# duckypad.net
KiCad netlist of a schematic drawn in EAGLE
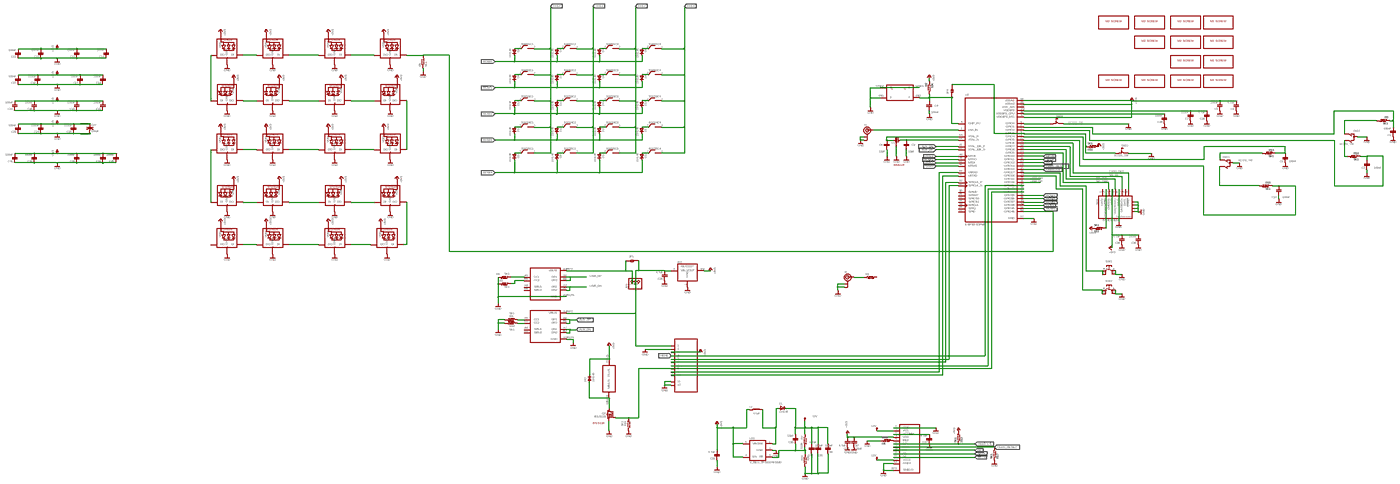
[diagram p0: schematic, sheet 1, overview]
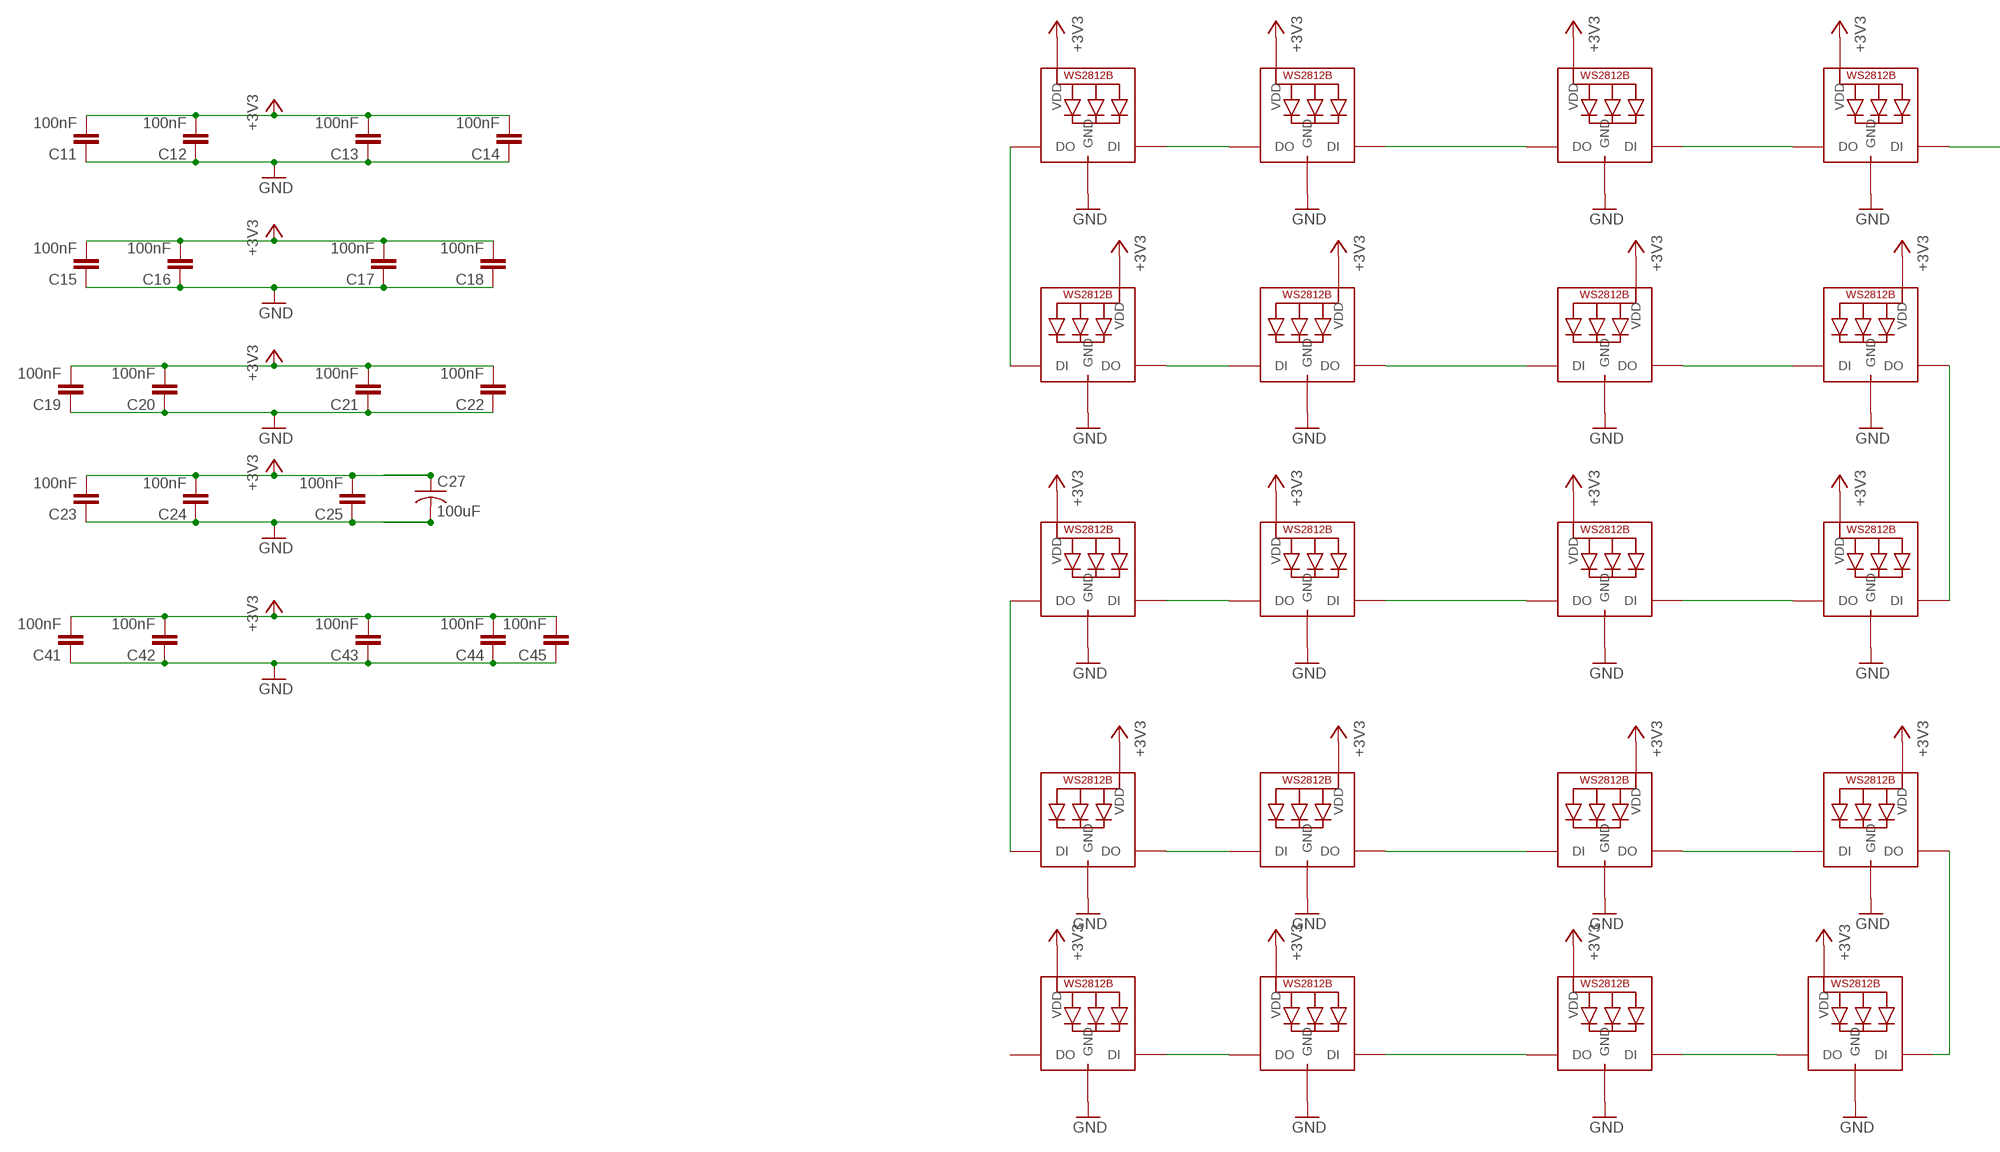
[diagram p1: schematic, sheet 1, part 1 of 4]
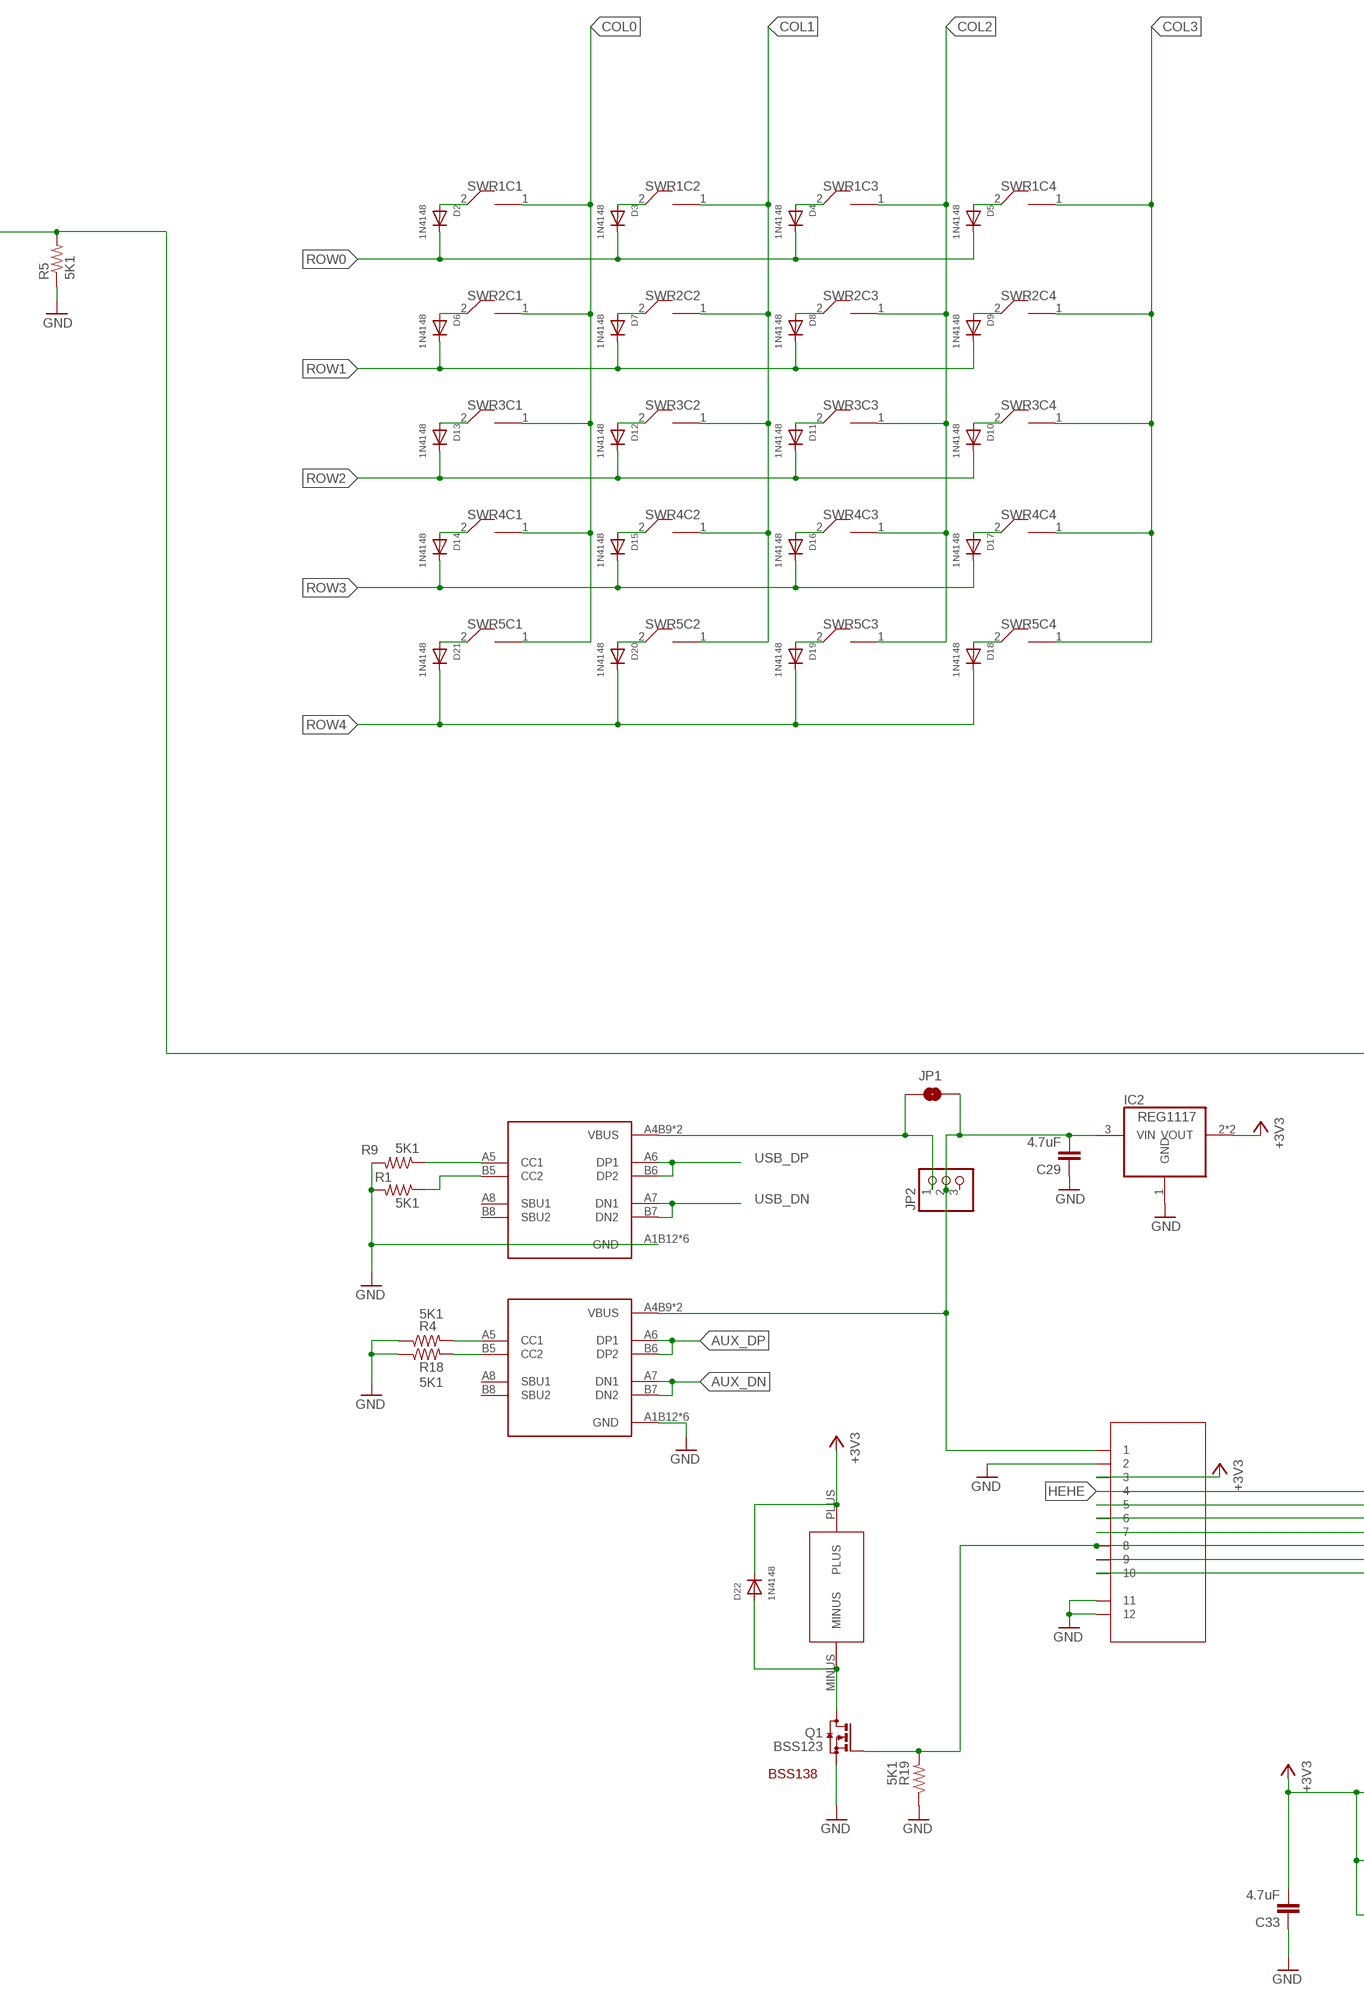
[diagram p2: schematic, sheet 1, part 2 of 4]
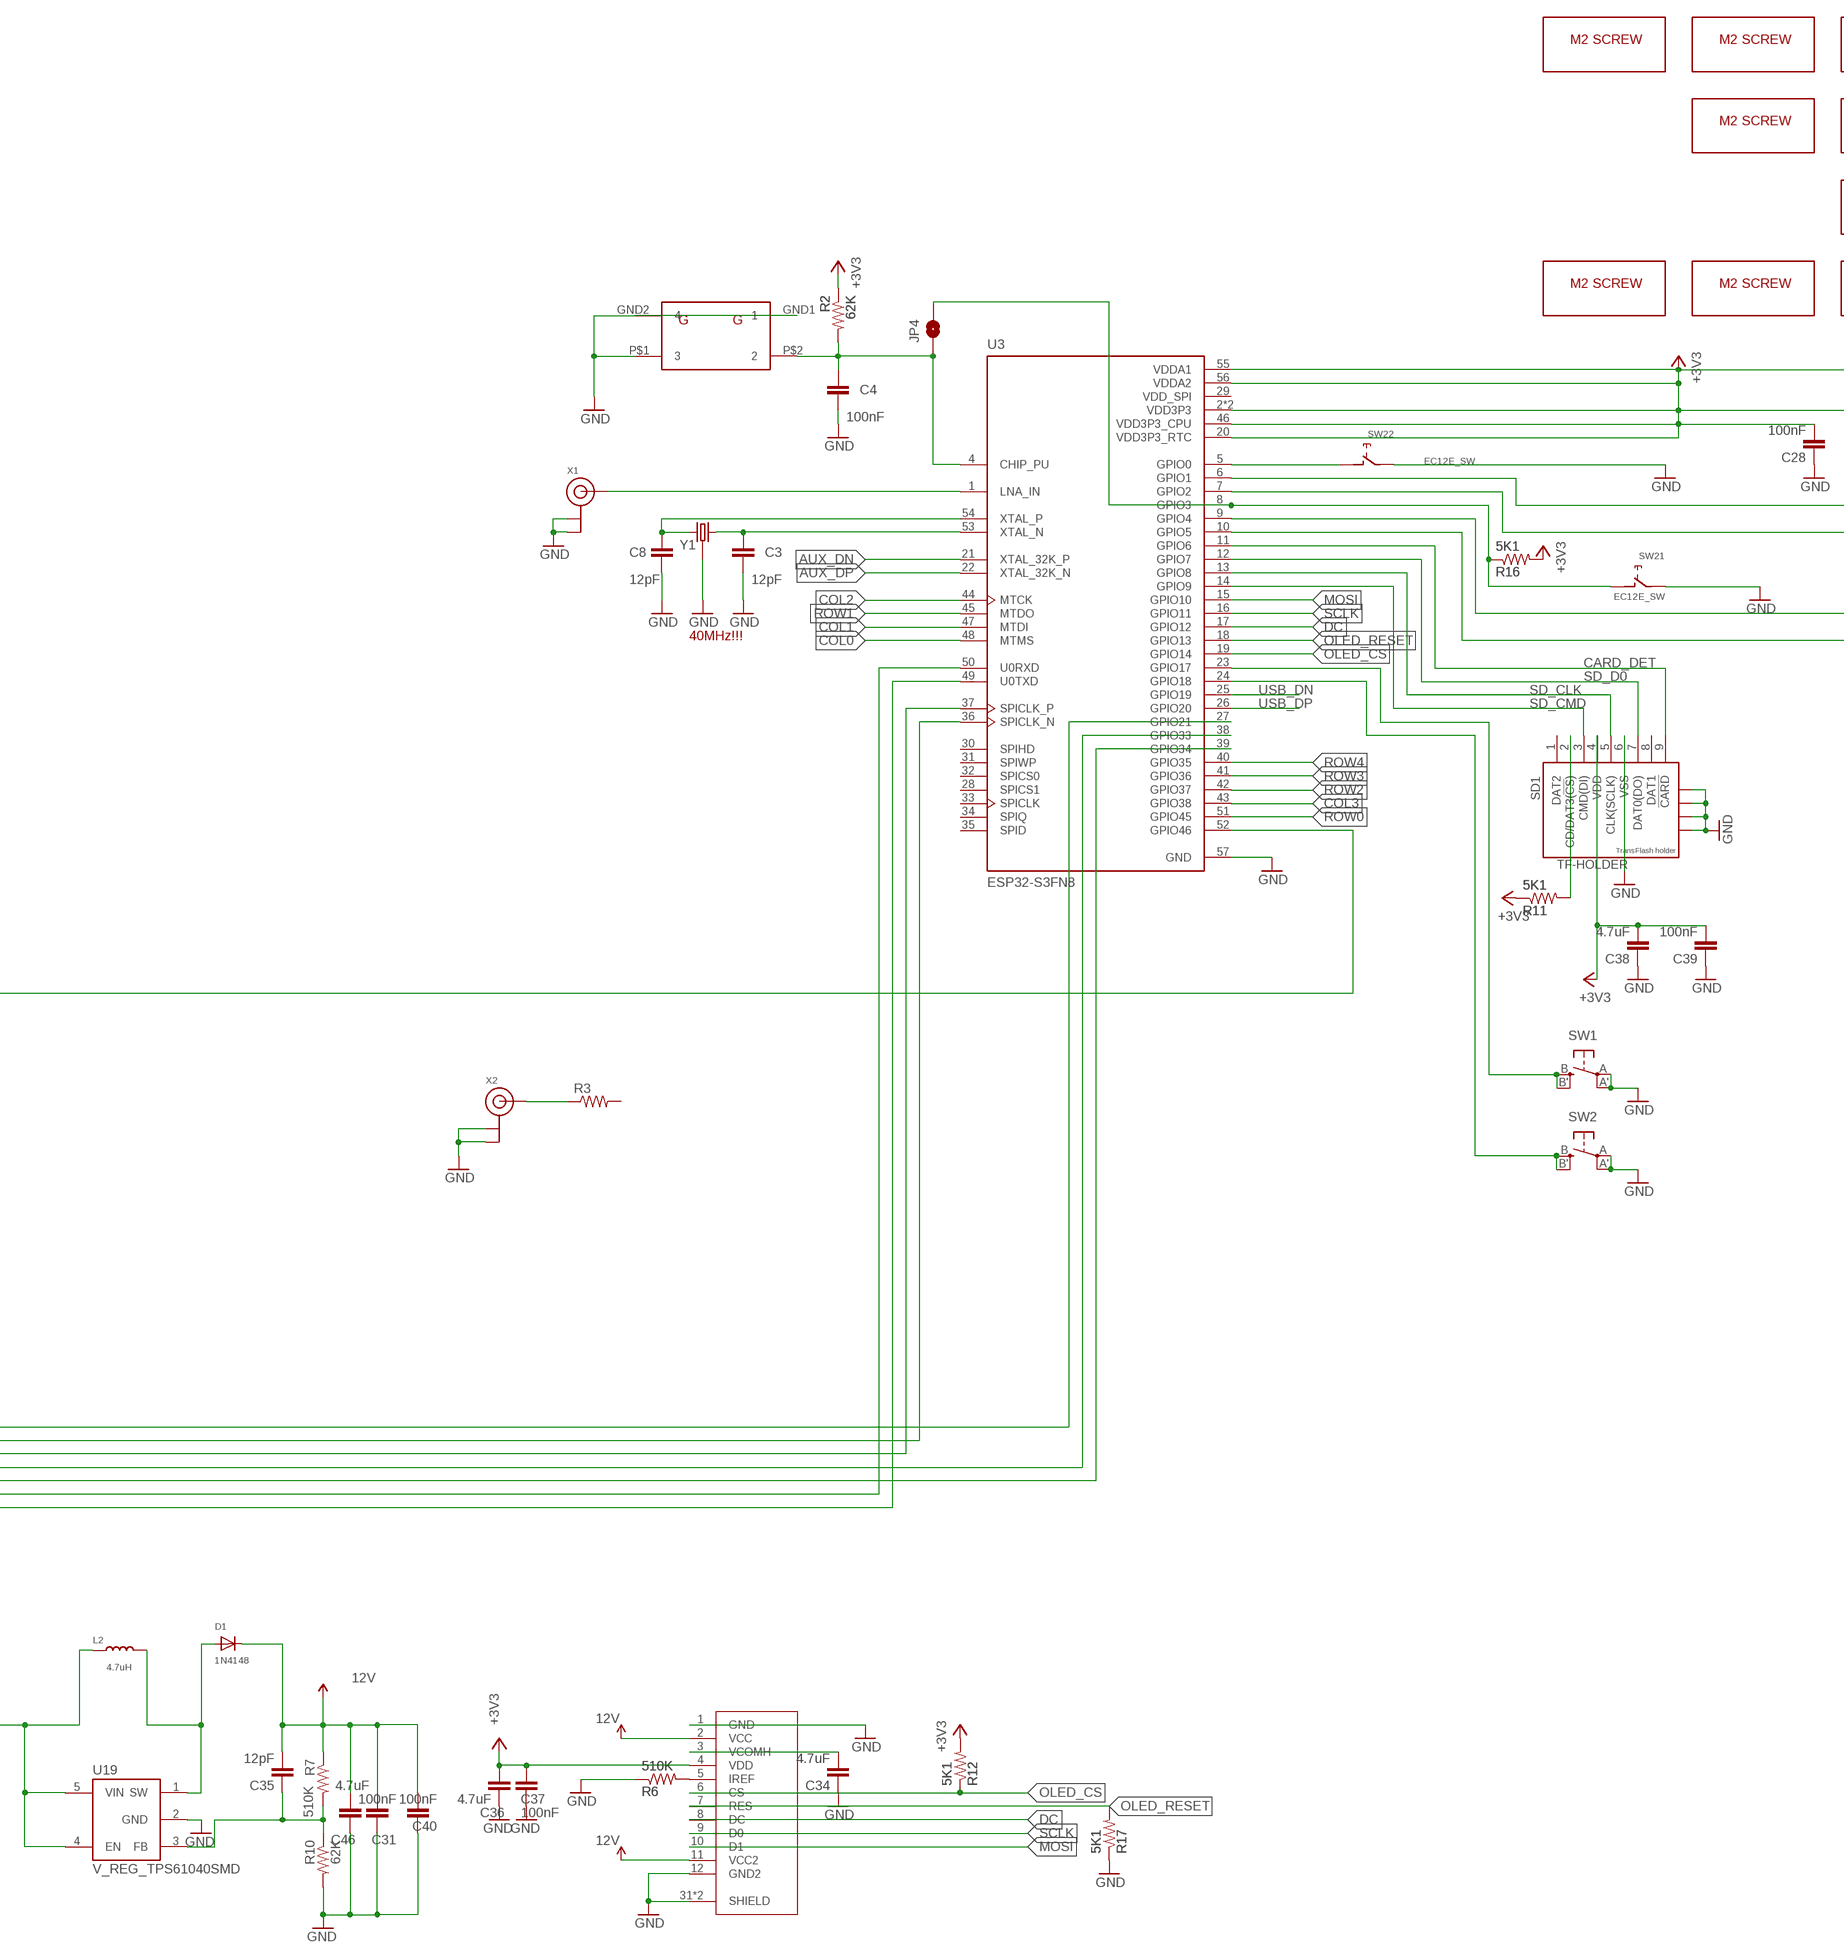
[diagram p3: schematic, sheet 1, part 3 of 4]
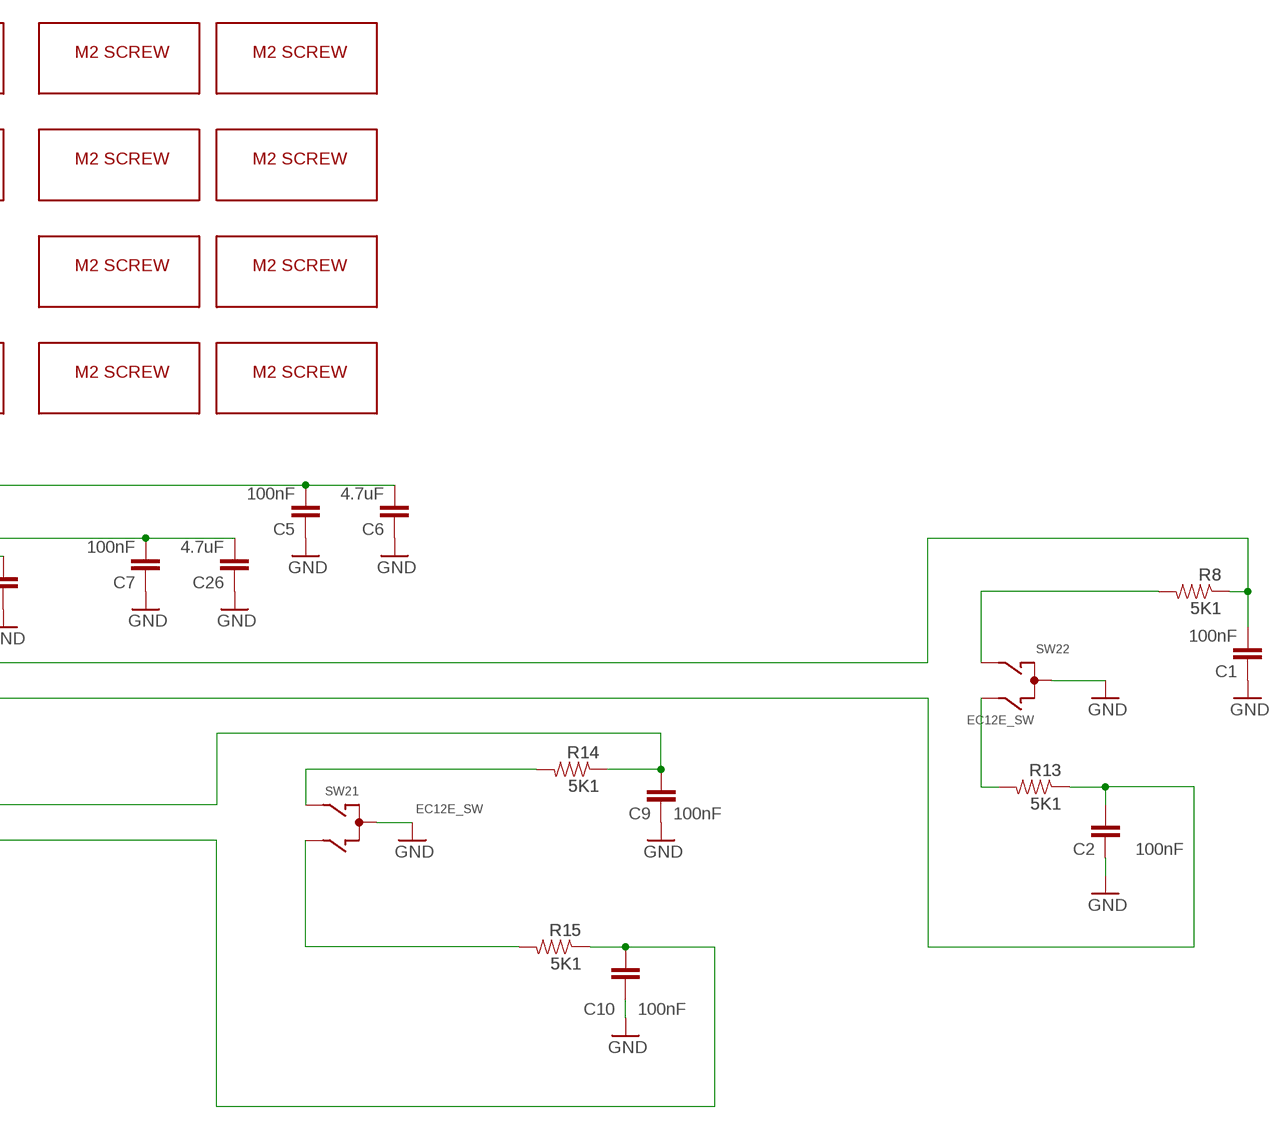
[diagram p4: schematic, sheet 1, part 4 of 4]

(export (version "E")
  (design (tool "Eeschema 10.0.6"))
  (components
    (comp (ref "BZ1")
      (value "BUZZ40402")
      (footprint "eagle-import:BUZZ")
      (libsource (lib "eagle-import") (part "BUZZ40402"))
    )
    (comp (ref "C1")
      (value "100nF")
      (footprint "eagle-import:0805")
      (libsource (lib "eagle-import") (part "CAP0805"))
    )
    (comp (ref "C2")
      (value "100nF")
      (footprint "eagle-import:0805")
      (libsource (lib "eagle-import") (part "CAP0805"))
    )
    (comp (ref "C3")
      (value "12pF")
      (footprint "eagle-import:0805")
      (libsource (lib "eagle-import") (part "CAP0805"))
    )
    (comp (ref "C4")
      (value "100nF")
      (footprint "eagle-import:0805")
      (libsource (lib "eagle-import") (part "CAP0805"))
    )
    (comp (ref "C5")
      (value "100nF")
      (footprint "eagle-import:0805")
      (libsource (lib "eagle-import") (part "CAP0805"))
    )
    (comp (ref "C6")
      (value "4.7uF")
      (footprint "eagle-import:0805")
      (libsource (lib "eagle-import") (part "CAP0805"))
    )
    (comp (ref "C7")
      (value "100nF")
      (footprint "eagle-import:0805")
      (libsource (lib "eagle-import") (part "CAP0805"))
    )
    (comp (ref "C8")
      (value "12pF")
      (footprint "eagle-import:0805")
      (libsource (lib "eagle-import") (part "CAP0805"))
    )
    (comp (ref "C9")
      (value "100nF")
      (footprint "eagle-import:0805")
      (libsource (lib "eagle-import") (part "CAP0805"))
    )
    (comp (ref "C10")
      (value "100nF")
      (footprint "eagle-import:0805")
      (libsource (lib "eagle-import") (part "CAP0805"))
    )
    (comp (ref "C11")
      (value "100nF")
      (footprint "eagle-import:0805")
      (libsource (lib "eagle-import") (part "CAP0805"))
    )
    (comp (ref "C12")
      (value "100nF")
      (footprint "eagle-import:0805")
      (libsource (lib "eagle-import") (part "CAP0805"))
    )
    (comp (ref "C13")
      (value "100nF")
      (footprint "eagle-import:0805")
      (libsource (lib "eagle-import") (part "CAP0805"))
    )
    (comp (ref "C14")
      (value "100nF")
      (footprint "eagle-import:0805")
      (libsource (lib "eagle-import") (part "CAP0805"))
    )
    (comp (ref "C15")
      (value "100nF")
      (footprint "eagle-import:0805")
      (libsource (lib "eagle-import") (part "CAP0805"))
    )
    (comp (ref "C16")
      (value "100nF")
      (footprint "eagle-import:0805")
      (libsource (lib "eagle-import") (part "CAP0805"))
    )
    (comp (ref "C17")
      (value "100nF")
      (footprint "eagle-import:0805")
      (libsource (lib "eagle-import") (part "CAP0805"))
    )
    (comp (ref "C18")
      (value "100nF")
      (footprint "eagle-import:0805")
      (libsource (lib "eagle-import") (part "CAP0805"))
    )
    (comp (ref "C19")
      (value "100nF")
      (footprint "eagle-import:0805")
      (libsource (lib "eagle-import") (part "CAP0805"))
    )
    (comp (ref "C20")
      (value "100nF")
      (footprint "eagle-import:0805")
      (libsource (lib "eagle-import") (part "CAP0805"))
    )
    (comp (ref "C21")
      (value "100nF")
      (footprint "eagle-import:0805")
      (libsource (lib "eagle-import") (part "CAP0805"))
    )
    (comp (ref "C22")
      (value "100nF")
      (footprint "eagle-import:0805")
      (libsource (lib "eagle-import") (part "CAP0805"))
    )
    (comp (ref "C23")
      (value "100nF")
      (footprint "eagle-import:0805")
      (libsource (lib "eagle-import") (part "CAP0805"))
    )
    (comp (ref "C24")
      (value "100nF")
      (footprint "eagle-import:0805")
      (libsource (lib "eagle-import") (part "CAP0805"))
    )
    (comp (ref "C25")
      (value "100nF")
      (footprint "eagle-import:0805")
      (libsource (lib "eagle-import") (part "CAP0805"))
    )
    (comp (ref "C26")
      (value "4.7uF")
      (footprint "eagle-import:0805")
      (libsource (lib "eagle-import") (part "CAP0805"))
    )
    (comp (ref "C27")
      (value "100uF")
      (footprint "eagle-import:C1210")
      (libsource (lib "eagle-import") (part "C-USC1210"))
    )
    (comp (ref "C28")
      (value "100nF")
      (footprint "eagle-import:0805")
      (libsource (lib "eagle-import") (part "CAP0805"))
    )
    (comp (ref "C29")
      (value "4.7uF")
      (footprint "eagle-import:0805")
      (libsource (lib "eagle-import") (part "CAP0805"))
    )
    (comp (ref "C31")
      (value "100nF")
      (footprint "eagle-import:0805")
      (libsource (lib "eagle-import") (part "CAP0805"))
    )
    (comp (ref "C33")
      (value "4.7uF")
      (footprint "eagle-import:0805")
      (libsource (lib "eagle-import") (part "CAP0805"))
    )
    (comp (ref "C34")
      (value "4.7uF")
      (footprint "eagle-import:0805")
      (libsource (lib "eagle-import") (part "CAP0805"))
    )
    (comp (ref "C35")
      (value "12pF")
      (footprint "eagle-import:0805")
      (libsource (lib "eagle-import") (part "CAP0805"))
    )
    (comp (ref "C36")
      (value "4.7uF")
      (footprint "eagle-import:0805")
      (libsource (lib "eagle-import") (part "CAP0805"))
    )
    (comp (ref "C37")
      (value "100nF")
      (footprint "eagle-import:0805")
      (libsource (lib "eagle-import") (part "CAP0805"))
    )
    (comp (ref "C38")
      (value "4.7uF")
      (footprint "eagle-import:0805")
      (libsource (lib "eagle-import") (part "CAP0805"))
    )
    (comp (ref "C39")
      (value "100nF")
      (footprint "eagle-import:0805")
      (libsource (lib "eagle-import") (part "CAP0805"))
    )
    (comp (ref "C40")
      (value "100nF")
      (footprint "eagle-import:0805")
      (libsource (lib "eagle-import") (part "CAP0805"))
    )
    (comp (ref "C41")
      (value "100nF")
      (footprint "eagle-import:0805")
      (libsource (lib "eagle-import") (part "CAP0805"))
    )
    (comp (ref "C42")
      (value "100nF")
      (footprint "eagle-import:0805")
      (libsource (lib "eagle-import") (part "CAP0805"))
    )
    (comp (ref "C43")
      (value "100nF")
      (footprint "eagle-import:0805")
      (libsource (lib "eagle-import") (part "CAP0805"))
    )
    (comp (ref "C44")
      (value "100nF")
      (footprint "eagle-import:0805")
      (libsource (lib "eagle-import") (part "CAP0805"))
    )
    (comp (ref "C45")
      (value "100nF")
      (footprint "eagle-import:0805")
      (libsource (lib "eagle-import") (part "CAP0805"))
    )
    (comp (ref "C46")
      (value "4.7uF")
      (footprint "eagle-import:0805")
      (libsource (lib "eagle-import") (part "CAP0805"))
    )
    (comp (ref "D1")
      (value "1N4148")
      (footprint "eagle-import:ADAFRUIT_CHANGED_SOD-123")
      (libsource (lib "eagle-import") (part "ADAFRUIT_CHANGED_DIODESOD-123"))
    )
    (comp (ref "D2")
      (value "1N4148")
      (footprint "eagle-import:ADAFRUIT_CHANGED_SOD-123")
      (libsource (lib "eagle-import") (part "ADAFRUIT_CHANGED_DIODESOD-123"))
    )
    (comp (ref "D3")
      (value "1N4148")
      (footprint "eagle-import:ADAFRUIT_CHANGED_SOD-123")
      (libsource (lib "eagle-import") (part "ADAFRUIT_CHANGED_DIODESOD-123"))
    )
    (comp (ref "D4")
      (value "1N4148")
      (footprint "eagle-import:ADAFRUIT_CHANGED_SOD-123")
      (libsource (lib "eagle-import") (part "ADAFRUIT_CHANGED_DIODESOD-123"))
    )
    (comp (ref "D5")
      (value "1N4148")
      (footprint "eagle-import:ADAFRUIT_CHANGED_SOD-123")
      (libsource (lib "eagle-import") (part "ADAFRUIT_CHANGED_DIODESOD-123"))
    )
    (comp (ref "D6")
      (value "1N4148")
      (footprint "eagle-import:ADAFRUIT_CHANGED_SOD-123")
      (libsource (lib "eagle-import") (part "ADAFRUIT_CHANGED_DIODESOD-123"))
    )
    (comp (ref "D7")
      (value "1N4148")
      (footprint "eagle-import:ADAFRUIT_CHANGED_SOD-123")
      (libsource (lib "eagle-import") (part "ADAFRUIT_CHANGED_DIODESOD-123"))
    )
    (comp (ref "D8")
      (value "1N4148")
      (footprint "eagle-import:ADAFRUIT_CHANGED_SOD-123")
      (libsource (lib "eagle-import") (part "ADAFRUIT_CHANGED_DIODESOD-123"))
    )
    (comp (ref "D9")
      (value "1N4148")
      (footprint "eagle-import:ADAFRUIT_CHANGED_SOD-123")
      (libsource (lib "eagle-import") (part "ADAFRUIT_CHANGED_DIODESOD-123"))
    )
    (comp (ref "D10")
      (value "1N4148")
      (footprint "eagle-import:ADAFRUIT_CHANGED_SOD-123")
      (libsource (lib "eagle-import") (part "ADAFRUIT_CHANGED_DIODESOD-123"))
    )
    (comp (ref "D11")
      (value "1N4148")
      (footprint "eagle-import:ADAFRUIT_CHANGED_SOD-123")
      (libsource (lib "eagle-import") (part "ADAFRUIT_CHANGED_DIODESOD-123"))
    )
    (comp (ref "D12")
      (value "1N4148")
      (footprint "eagle-import:ADAFRUIT_CHANGED_SOD-123")
      (libsource (lib "eagle-import") (part "ADAFRUIT_CHANGED_DIODESOD-123"))
    )
    (comp (ref "D13")
      (value "1N4148")
      (footprint "eagle-import:ADAFRUIT_CHANGED_SOD-123")
      (libsource (lib "eagle-import") (part "ADAFRUIT_CHANGED_DIODESOD-123"))
    )
    (comp (ref "D14")
      (value "1N4148")
      (footprint "eagle-import:ADAFRUIT_CHANGED_SOD-123")
      (libsource (lib "eagle-import") (part "ADAFRUIT_CHANGED_DIODESOD-123"))
    )
    (comp (ref "D15")
      (value "1N4148")
      (footprint "eagle-import:ADAFRUIT_CHANGED_SOD-123")
      (libsource (lib "eagle-import") (part "ADAFRUIT_CHANGED_DIODESOD-123"))
    )
    (comp (ref "D16")
      (value "1N4148")
      (footprint "eagle-import:ADAFRUIT_CHANGED_SOD-123")
      (libsource (lib "eagle-import") (part "ADAFRUIT_CHANGED_DIODESOD-123"))
    )
    (comp (ref "D17")
      (value "1N4148")
      (footprint "eagle-import:ADAFRUIT_CHANGED_SOD-123")
      (libsource (lib "eagle-import") (part "ADAFRUIT_CHANGED_DIODESOD-123"))
    )
    (comp (ref "D18")
      (value "1N4148")
      (footprint "eagle-import:ADAFRUIT_CHANGED_SOD-123")
      (libsource (lib "eagle-import") (part "ADAFRUIT_CHANGED_DIODESOD-123"))
    )
    (comp (ref "D19")
      (value "1N4148")
      (footprint "eagle-import:ADAFRUIT_CHANGED_SOD-123")
      (libsource (lib "eagle-import") (part "ADAFRUIT_CHANGED_DIODESOD-123"))
    )
    (comp (ref "D20")
      (value "1N4148")
      (footprint "eagle-import:ADAFRUIT_CHANGED_SOD-123")
      (libsource (lib "eagle-import") (part "ADAFRUIT_CHANGED_DIODESOD-123"))
    )
    (comp (ref "D21")
      (value "1N4148")
      (footprint "eagle-import:ADAFRUIT_CHANGED_SOD-123")
      (libsource (lib "eagle-import") (part "ADAFRUIT_CHANGED_DIODESOD-123"))
    )
    (comp (ref "D22")
      (value "1N4148")
      (footprint "eagle-import:ADAFRUIT_CHANGED_SOD-123")
      (libsource (lib "eagle-import") (part "ADAFRUIT_CHANGED_DIODESOD-123"))
    )
    (comp (ref "IC2")
      (value "REG1117")
      (footprint "eagle-import:SOT223")
      (libsource (lib "eagle-import") (part "REG1117"))
    )
    (comp (ref "JP1")
      (value "JUMPER-SMT_2_NO_NO-SILK")
      (footprint "eagle-import:SMT-JUMPER_2_NO_NO-SILK")
      (libsource (lib "eagle-import") (part "JUMPER-SMT_2_NO_NO-SILK"))
    )
    (comp (ref "JP2")
      (value "PINHD-1X3CB")
      (footprint "eagle-import:1X03-CLEANBIG")
      (libsource (lib "eagle-import") (part "PINHD-1X3CB"))
    )
    (comp (ref "JP4")
      (value "JUMPER-SMT_2_NO_NO-SILK")
      (footprint "eagle-import:SMT-JUMPER_2_NO_NO-SILK")
      (libsource (lib "eagle-import") (part "JUMPER-SMT_2_NO_NO-SILK"))
    )
    (comp (ref "L2")
      (value "4.7uH")
      (footprint "eagle-import:L4030")
      (libsource (lib "eagle-import") (part "L-4030"))
    )
    (comp (ref "LED_R1C1")
      (value "WS2812B")
      (footprint "eagle-import:REVERSE_MNT")
      (libsource (lib "eagle-import") (part "WS2812B"))
    )
    (comp (ref "LED_R1C2")
      (value "WS2812B")
      (footprint "eagle-import:REVERSE_MNT")
      (libsource (lib "eagle-import") (part "WS2812B"))
    )
    (comp (ref "LED_R1C3")
      (value "WS2812B")
      (footprint "eagle-import:REVERSE_MNT")
      (libsource (lib "eagle-import") (part "WS2812B"))
    )
    (comp (ref "LED_R1C4")
      (value "WS2812B")
      (footprint "eagle-import:REVERSE_MNT")
      (libsource (lib "eagle-import") (part "WS2812B"))
    )
    (comp (ref "LED_R2C1")
      (value "WS2812B")
      (footprint "eagle-import:REVERSE_MNT")
      (libsource (lib "eagle-import") (part "WS2812B"))
    )
    (comp (ref "LED_R2C2")
      (value "WS2812B")
      (footprint "eagle-import:REVERSE_MNT")
      (libsource (lib "eagle-import") (part "WS2812B"))
    )
    (comp (ref "LED_R2C3")
      (value "WS2812B")
      (footprint "eagle-import:REVERSE_MNT")
      (libsource (lib "eagle-import") (part "WS2812B"))
    )
    (comp (ref "LED_R2C4")
      (value "WS2812B")
      (footprint "eagle-import:REVERSE_MNT")
      (libsource (lib "eagle-import") (part "WS2812B"))
    )
    (comp (ref "LED_R3C1")
      (value "WS2812B")
      (footprint "eagle-import:REVERSE_MNT")
      (libsource (lib "eagle-import") (part "WS2812B"))
    )
    (comp (ref "LED_R3C2")
      (value "WS2812B")
      (footprint "eagle-import:REVERSE_MNT")
      (libsource (lib "eagle-import") (part "WS2812B"))
    )
    (comp (ref "LED_R3C3")
      (value "WS2812B")
      (footprint "eagle-import:REVERSE_MNT")
      (libsource (lib "eagle-import") (part "WS2812B"))
    )
    (comp (ref "LED_R3C4")
      (value "WS2812B")
      (footprint "eagle-import:REVERSE_MNT")
      (libsource (lib "eagle-import") (part "WS2812B"))
    )
    (comp (ref "LED_R4C1")
      (value "WS2812B")
      (footprint "eagle-import:REVERSE_MNT")
      (libsource (lib "eagle-import") (part "WS2812B"))
    )
    (comp (ref "LED_R4C2")
      (value "WS2812B")
      (footprint "eagle-import:REVERSE_MNT")
      (libsource (lib "eagle-import") (part "WS2812B"))
    )
    (comp (ref "LED_R4C3")
      (value "WS2812B")
      (footprint "eagle-import:REVERSE_MNT")
      (libsource (lib "eagle-import") (part "WS2812B"))
    )
    (comp (ref "LED_R4C4")
      (value "WS2812B")
      (footprint "eagle-import:REVERSE_MNT")
      (libsource (lib "eagle-import") (part "WS2812B"))
    )
    (comp (ref "LED_R5C1")
      (value "WS2812B")
      (footprint "eagle-import:REVERSE_MNT")
      (libsource (lib "eagle-import") (part "WS2812B"))
    )
    (comp (ref "LED_R5C2")
      (value "WS2812B")
      (footprint "eagle-import:REVERSE_MNT")
      (libsource (lib "eagle-import") (part "WS2812B"))
    )
    (comp (ref "LED_R5C3")
      (value "WS2812B")
      (footprint "eagle-import:REVERSE_MNT")
      (libsource (lib "eagle-import") (part "WS2812B"))
    )
    (comp (ref "LED_R5C4")
      (value "WS2812B")
      (footprint "eagle-import:REVERSE_MNT")
      (libsource (lib "eagle-import") (part "WS2812B"))
    )
    (comp (ref "Q1")
      (value "BSS123")
      (footprint "eagle-import:SOT23")
      (libsource (lib "eagle-import") (part "BSS123"))
    )
    (comp (ref "R1")
      (value "5K1")
      (footprint "eagle-import:0805")
      (libsource (lib "eagle-import") (part "joyAnalog_RESISTOR0805-RES"))
    )
    (comp (ref "R2")
      (value "62K")
      (footprint "eagle-import:0805")
      (libsource (lib "eagle-import") (part "joyAnalog_RESISTOR0805-RES"))
    )
    (comp (ref "R3")
      (value "R-US_R2010")
      (footprint "eagle-import:R2010")
      (libsource (lib "eagle-import") (part "R-US_R2010"))
    )
    (comp (ref "R4")
      (value "5K1")
      (footprint "eagle-import:0805")
      (libsource (lib "eagle-import") (part "joyAnalog_RESISTOR0805-RES"))
    )
    (comp (ref "R5")
      (value "5K1")
      (footprint "eagle-import:0805")
      (libsource (lib "eagle-import") (part "RESISTOR0805-RES"))
    )
    (comp (ref "R6")
      (value "510K")
      (footprint "eagle-import:0805")
      (libsource (lib "eagle-import") (part "joyAnalog_RESISTOR0805-RES"))
    )
    (comp (ref "R7")
      (value "510K")
      (footprint "eagle-import:0805")
      (libsource (lib "eagle-import") (part "joyAnalog_RESISTOR0805-RES"))
    )
    (comp (ref "R8")
      (value "5K1")
      (footprint "eagle-import:0805")
      (libsource (lib "eagle-import") (part "joyAnalog_RESISTOR0805-RES"))
    )
    (comp (ref "R9")
      (value "5K1")
      (footprint "eagle-import:0805")
      (libsource (lib "eagle-import") (part "joyAnalog_RESISTOR0805-RES"))
    )
    (comp (ref "R10")
      (value "62K")
      (footprint "eagle-import:0805")
      (libsource (lib "eagle-import") (part "joyAnalog_RESISTOR0805-RES"))
    )
    (comp (ref "R11")
      (value "5K1")
      (footprint "eagle-import:0805")
      (libsource (lib "eagle-import") (part "joyAnalog_RESISTOR0805-RES"))
    )
    (comp (ref "R12")
      (value "5K1")
      (footprint "eagle-import:0805")
      (libsource (lib "eagle-import") (part "joyAnalog_RESISTOR0805-RES"))
    )
    (comp (ref "R13")
      (value "5K1")
      (footprint "eagle-import:0805")
      (libsource (lib "eagle-import") (part "joyAnalog_RESISTOR0805-RES"))
    )
    (comp (ref "R14")
      (value "5K1")
      (footprint "eagle-import:0805")
      (libsource (lib "eagle-import") (part "joyAnalog_RESISTOR0805-RES"))
    )
    (comp (ref "R15")
      (value "5K1")
      (footprint "eagle-import:0805")
      (libsource (lib "eagle-import") (part "joyAnalog_RESISTOR0805-RES"))
    )
    (comp (ref "R16")
      (value "5K1")
      (footprint "eagle-import:0805")
      (libsource (lib "eagle-import") (part "joyAnalog_RESISTOR0805-RES"))
    )
    (comp (ref "R17")
      (value "5K1")
      (footprint "eagle-import:0805")
      (libsource (lib "eagle-import") (part "joyAnalog_RESISTOR0805-RES"))
    )
    (comp (ref "R18")
      (value "5K1")
      (footprint "eagle-import:0805")
      (libsource (lib "eagle-import") (part "joyAnalog_RESISTOR0805-RES"))
    )
    (comp (ref "R19")
      (value "5K1")
      (footprint "eagle-import:0805")
      (libsource (lib "eagle-import") (part "joyAnalog_RESISTOR0805-RES"))
    )
    (comp (ref "SD1")
      (value "TF-HOLDER")
      (footprint "eagle-import:TF-PULL")
      (libsource (lib "eagle-import") (part "TF-HOLDER"))
    )
    (comp (ref "SH1")
      (value "SH10P")
      (footprint "eagle-import:DUCKYPAD_SM12B-SSR-H-TB")
      (libsource (lib "eagle-import") (part "SH10P"))
    )
    (comp (ref "SW1")
      (value "SPST_TACT-EVQQ2")
      (footprint "eagle-import:EVQ-Q2")
      (libsource (lib "eagle-import") (part "SPST_TACT-EVQQ2"))
    )
    (comp (ref "SW2")
      (value "SPST_TACT-EVQQ2")
      (footprint "eagle-import:EVQ-Q2")
      (libsource (lib "eagle-import") (part "SPST_TACT-EVQQ2"))
    )
    (comp (ref "SW3")
      (value "3POS_SLIDE_SWITCH_324_SW")
      (footprint "eagle-import:SIDEPUSH")
      (libsource (lib "eagle-import") (part "3POS_SLIDE_SWITCH_324_SW"))
    )
    (comp (ref "SW21")
      (value "EC12E_SW")
      (footprint "eagle-import:ALPS_EC12E_SW")
      (fields (field (name "MPN") "EC12E2424407"))
      (libsource (lib "eagle-import") (part "EC12E_SW"))
    )
    (comp (ref "SW22")
      (value "EC12E_SW")
      (footprint "eagle-import:ALPS_EC12E_SW")
      (fields (field (name "MPN") "EC12E2424407"))
      (libsource (lib "eagle-import") (part "EC12E_SW"))
    )
    (comp (ref "SWR1C1")
      (value "KAILH_SWITCH_SOCKET_KAILH_SWITCH_SOCKET")
      (footprint "eagle-import:KAILH_SWITCH_SOCKET_SWITCH_SOCKET")
      (libsource (lib "eagle-import") (part "KAILH_SWITCH_SOCKET_KAILH_SWITCH_SOCKET"))
    )
    (comp (ref "SWR1C2")
      (value "KAILH_SWITCH_SOCKET_KAILH_SWITCH_SOCKET")
      (footprint "eagle-import:KAILH_SWITCH_SOCKET_SWITCH_SOCKET")
      (libsource (lib "eagle-import") (part "KAILH_SWITCH_SOCKET_KAILH_SWITCH_SOCKET"))
    )
    (comp (ref "SWR1C3")
      (value "KAILH_SWITCH_SOCKET_KAILH_SWITCH_SOCKET")
      (footprint "eagle-import:KAILH_SWITCH_SOCKET_SWITCH_SOCKET")
      (libsource (lib "eagle-import") (part "KAILH_SWITCH_SOCKET_KAILH_SWITCH_SOCKET"))
    )
    (comp (ref "SWR1C4")
      (value "KAILH_SWITCH_SOCKET_KAILH_SWITCH_SOCKET")
      (footprint "eagle-import:KAILH_SWITCH_SOCKET_SWITCH_SOCKET")
      (libsource (lib "eagle-import") (part "KAILH_SWITCH_SOCKET_KAILH_SWITCH_SOCKET"))
    )
    (comp (ref "SWR2C1")
      (value "KAILH_SWITCH_SOCKET_KAILH_SWITCH_SOCKET")
      (footprint "eagle-import:KAILH_SWITCH_SOCKET_SWITCH_SOCKET")
      (libsource (lib "eagle-import") (part "KAILH_SWITCH_SOCKET_KAILH_SWITCH_SOCKET"))
    )
    (comp (ref "SWR2C2")
      (value "KAILH_SWITCH_SOCKET_KAILH_SWITCH_SOCKET")
      (footprint "eagle-import:KAILH_SWITCH_SOCKET_SWITCH_SOCKET")
      (libsource (lib "eagle-import") (part "KAILH_SWITCH_SOCKET_KAILH_SWITCH_SOCKET"))
    )
    (comp (ref "SWR2C3")
      (value "KAILH_SWITCH_SOCKET_KAILH_SWITCH_SOCKET")
      (footprint "eagle-import:KAILH_SWITCH_SOCKET_SWITCH_SOCKET")
      (libsource (lib "eagle-import") (part "KAILH_SWITCH_SOCKET_KAILH_SWITCH_SOCKET"))
    )
    (comp (ref "SWR2C4")
      (value "KAILH_SWITCH_SOCKET_KAILH_SWITCH_SOCKET")
      (footprint "eagle-import:KAILH_SWITCH_SOCKET_SWITCH_SOCKET")
      (libsource (lib "eagle-import") (part "KAILH_SWITCH_SOCKET_KAILH_SWITCH_SOCKET"))
    )
    (comp (ref "SWR3C1")
      (value "KAILH_SWITCH_SOCKET_KAILH_SWITCH_SOCKET")
      (footprint "eagle-import:KAILH_SWITCH_SOCKET_SWITCH_SOCKET")
      (libsource (lib "eagle-import") (part "KAILH_SWITCH_SOCKET_KAILH_SWITCH_SOCKET"))
    )
    (comp (ref "SWR3C2")
      (value "KAILH_SWITCH_SOCKET_KAILH_SWITCH_SOCKET")
      (footprint "eagle-import:KAILH_SWITCH_SOCKET_SWITCH_SOCKET")
      (libsource (lib "eagle-import") (part "KAILH_SWITCH_SOCKET_KAILH_SWITCH_SOCKET"))
    )
    (comp (ref "SWR3C3")
      (value "KAILH_SWITCH_SOCKET_KAILH_SWITCH_SOCKET")
      (footprint "eagle-import:KAILH_SWITCH_SOCKET_SWITCH_SOCKET")
      (libsource (lib "eagle-import") (part "KAILH_SWITCH_SOCKET_KAILH_SWITCH_SOCKET"))
    )
    (comp (ref "SWR3C4")
      (value "KAILH_SWITCH_SOCKET_KAILH_SWITCH_SOCKET")
      (footprint "eagle-import:KAILH_SWITCH_SOCKET_SWITCH_SOCKET")
      (libsource (lib "eagle-import") (part "KAILH_SWITCH_SOCKET_KAILH_SWITCH_SOCKET"))
    )
    (comp (ref "SWR4C1")
      (value "KAILH_SWITCH_SOCKET_KAILH_SWITCH_SOCKET")
      (footprint "eagle-import:KAILH_SWITCH_SOCKET_SWITCH_SOCKET")
      (libsource (lib "eagle-import") (part "KAILH_SWITCH_SOCKET_KAILH_SWITCH_SOCKET"))
    )
    (comp (ref "SWR4C2")
      (value "KAILH_SWITCH_SOCKET_KAILH_SWITCH_SOCKET")
      (footprint "eagle-import:KAILH_SWITCH_SOCKET_SWITCH_SOCKET")
      (libsource (lib "eagle-import") (part "KAILH_SWITCH_SOCKET_KAILH_SWITCH_SOCKET"))
    )
    (comp (ref "SWR4C3")
      (value "KAILH_SWITCH_SOCKET_KAILH_SWITCH_SOCKET")
      (footprint "eagle-import:KAILH_SWITCH_SOCKET_SWITCH_SOCKET")
      (libsource (lib "eagle-import") (part "KAILH_SWITCH_SOCKET_KAILH_SWITCH_SOCKET"))
    )
    (comp (ref "SWR4C4")
      (value "KAILH_SWITCH_SOCKET_KAILH_SWITCH_SOCKET")
      (footprint "eagle-import:KAILH_SWITCH_SOCKET_SWITCH_SOCKET")
      (libsource (lib "eagle-import") (part "KAILH_SWITCH_SOCKET_KAILH_SWITCH_SOCKET"))
    )
    (comp (ref "SWR5C1")
      (value "KAILH_SWITCH_SOCKET_KAILH_SWITCH_SOCKET")
      (footprint "eagle-import:KAILH_SWITCH_SOCKET_SWITCH_SOCKET")
      (libsource (lib "eagle-import") (part "KAILH_SWITCH_SOCKET_KAILH_SWITCH_SOCKET"))
    )
    (comp (ref "SWR5C2")
      (value "KAILH_SWITCH_SOCKET_KAILH_SWITCH_SOCKET")
      (footprint "eagle-import:KAILH_SWITCH_SOCKET_SWITCH_SOCKET")
      (libsource (lib "eagle-import") (part "KAILH_SWITCH_SOCKET_KAILH_SWITCH_SOCKET"))
    )
    (comp (ref "SWR5C3")
      (value "KAILH_SWITCH_SOCKET_KAILH_SWITCH_SOCKET")
      (footprint "eagle-import:KAILH_SWITCH_SOCKET_SWITCH_SOCKET")
      (libsource (lib "eagle-import") (part "KAILH_SWITCH_SOCKET_KAILH_SWITCH_SOCKET"))
    )
    (comp (ref "SWR5C4")
      (value "KAILH_SWITCH_SOCKET_KAILH_SWITCH_SOCKET")
      (footprint "eagle-import:KAILH_SWITCH_SOCKET_SWITCH_SOCKET")
      (libsource (lib "eagle-import") (part "KAILH_SWITCH_SOCKET_KAILH_SWITCH_SOCKET"))
    )
    (comp (ref "U$2")
      (value "OLED_OLED128")
      (footprint "eagle-import:OLED_LUL_UG-2864HSWEG01_1.3_WRAPAROUND")
      (libsource (lib "eagle-import") (part "OLED_OLED128"))
    )
    (comp (ref "U$7")
      (value "M2_SCREW_DEV")
      (footprint "eagle-import:M2_SCREW_FOOT")
      (libsource (lib "eagle-import") (part "M2_SCREW_DEV"))
    )
    (comp (ref "U$8")
      (value "M2_SCREW_DEV")
      (footprint "eagle-import:M2_SCREW_FOOT")
      (libsource (lib "eagle-import") (part "M2_SCREW_DEV"))
    )
    (comp (ref "U$9")
      (value "M2_SCREW_DEV")
      (footprint "eagle-import:M2_SCREW_FOOT")
      (libsource (lib "eagle-import") (part "M2_SCREW_DEV"))
    )
    (comp (ref "U$11")
      (value "M2_SCREW_DEV")
      (footprint "eagle-import:M2_SCREW_FOOT")
      (libsource (lib "eagle-import") (part "M2_SCREW_DEV"))
    )
    (comp (ref "U$12")
      (value "M2_SCREW_DEV")
      (footprint "eagle-import:M2_SCREW_FOOT")
      (libsource (lib "eagle-import") (part "M2_SCREW_DEV"))
    )
    (comp (ref "U$13")
      (value "M2_SCREW_DEV")
      (footprint "eagle-import:M2_SCREW_FOOT")
      (libsource (lib "eagle-import") (part "M2_SCREW_DEV"))
    )
    (comp (ref "U$14")
      (value "M2_SCREW_DEV")
      (footprint "eagle-import:M2_SCREW_FOOT")
      (libsource (lib "eagle-import") (part "M2_SCREW_DEV"))
    )
    (comp (ref "U$15")
      (value "M2_SCREW_DEV")
      (footprint "eagle-import:M2_SCREW_FOOT")
      (libsource (lib "eagle-import") (part "M2_SCREW_DEV"))
    )
    (comp (ref "U$16")
      (value "M2_SCREW_DEV")
      (footprint "eagle-import:M2_SCREW_FOOT")
      (libsource (lib "eagle-import") (part "M2_SCREW_DEV"))
    )
    (comp (ref "U$17")
      (value "M2_SCREW_DEV")
      (footprint "eagle-import:M2_SCREW_FOOT")
      (libsource (lib "eagle-import") (part "M2_SCREW_DEV"))
    )
    (comp (ref "U$20")
      (value "M2_SCREW_DEV")
      (footprint "eagle-import:M2_SCREW_FOOT")
      (libsource (lib "eagle-import") (part "M2_SCREW_DEV"))
    )
    (comp (ref "U$21")
      (value "M2_SCREW_DEV")
      (footprint "eagle-import:M2_SCREW_FOOT")
      (libsource (lib "eagle-import") (part "M2_SCREW_DEV"))
    )
    (comp (ref "U$22")
      (value "M2_SCREW_DEV")
      (footprint "eagle-import:M2_SCREW_FOOT")
      (libsource (lib "eagle-import") (part "M2_SCREW_DEV"))
    )
    (comp (ref "U1")
      (value "USBC_16P")
      (footprint "eagle-import:USBC_16P_FOOT")
      (libsource (lib "eagle-import") (part "USBC_16P"))
    )
    (comp (ref "U2")
      (value "USBC_16P")
      (footprint "eagle-import:USBC_16P_FOOT")
      (libsource (lib "eagle-import") (part "USBC_16P"))
    )
    (comp (ref "U3")
      (value "ESP32-S3FN8")
      (footprint "eagle-import:QFN40P700X700X90-57N")
      (fields (field (name "MF") "Espressif Systems"))
      (libsource (lib "eagle-import") (part "ESP32-S3FN8"))
    )
    (comp (ref "U19")
      (value "V_REG_TPS61040SMD")
      (footprint "eagle-import:SOT23-5")
      (libsource (lib "eagle-import") (part "V_REG_TPS61040SMD"))
    )
    (comp (ref "X1")
      (value "ANTENNA_U.FL")
      (footprint "eagle-import:U.FL")
      (libsource (lib "eagle-import") (part "ANTENNA_U.FL"))
    )
    (comp (ref "X2")
      (value "ANTENNA_U.FL")
      (footprint "eagle-import:U.FL")
      (libsource (lib "eagle-import") (part "ANTENNA_U.FL"))
    )
    (comp (ref "Y1")
      (value "16MHz_12pF")
      (footprint "eagle-import:CRYSTAL-SMD-3.2X2.5MM")
      (libsource (lib "eagle-import") (part "CRYSTAL-26MHZSMD-3.2X2.5"))
    )
  )
  (nets
    (net (code "1") (name "+3V3") (class "Default")
      (node (ref "BZ1") (pin "PLUS") (pinfunction "PLUS_PLUS") (pintype "bidirectional"))
      (node (ref "C11") (pin "2") (pinfunction "2_2") (pintype "passive"))
      (node (ref "C12") (pin "2") (pinfunction "2_2") (pintype "passive"))
      (node (ref "C13") (pin "2") (pinfunction "2_2") (pintype "passive"))
      (node (ref "C14") (pin "2") (pinfunction "2_2") (pintype "passive"))
      (node (ref "C15") (pin "2") (pinfunction "2_2") (pintype "passive"))
      (node (ref "C16") (pin "2") (pinfunction "2_2") (pintype "passive"))
      (node (ref "C17") (pin "2") (pinfunction "2_2") (pintype "passive"))
      (node (ref "C18") (pin "2") (pinfunction "2_2") (pintype "passive"))
      (node (ref "C19") (pin "2") (pinfunction "2_2") (pintype "passive"))
      (node (ref "C20") (pin "2") (pinfunction "2_2") (pintype "passive"))
      (node (ref "C21") (pin "2") (pinfunction "2_2") (pintype "passive"))
      (node (ref "C22") (pin "2") (pinfunction "2_2") (pintype "passive"))
      (node (ref "C23") (pin "2") (pinfunction "2_2") (pintype "passive"))
      (node (ref "C24") (pin "2") (pinfunction "2_2") (pintype "passive"))
      (node (ref "C25") (pin "2") (pinfunction "2_2") (pintype "passive"))
      (node (ref "C26") (pin "2") (pinfunction "2_2") (pintype "passive"))
      (node (ref "C27") (pin "1") (pinfunction "1_1") (pintype "passive"))
      (node (ref "C28") (pin "2") (pinfunction "2_2") (pintype "passive"))
      (node (ref "C33") (pin "2") (pinfunction "2_2") (pintype "passive"))
      (node (ref "C36") (pin "2") (pinfunction "2_2") (pintype "passive"))
      (node (ref "C37") (pin "2") (pinfunction "2_2") (pintype "passive"))
      (node (ref "C38") (pin "2") (pinfunction "2_2") (pintype "passive"))
      (node (ref "C39") (pin "2") (pinfunction "2_2") (pintype "passive"))
      (node (ref "C41") (pin "2") (pinfunction "2_2") (pintype "passive"))
      (node (ref "C42") (pin "2") (pinfunction "2_2") (pintype "passive"))
      (node (ref "C43") (pin "2") (pinfunction "2_2") (pintype "passive"))
      (node (ref "C44") (pin "2") (pinfunction "2_2") (pintype "passive"))
      (node (ref "C45") (pin "2") (pinfunction "2_2") (pintype "passive"))
      (node (ref "C5") (pin "2") (pinfunction "2_2") (pintype "passive"))
      (node (ref "C6") (pin "2") (pinfunction "2_2") (pintype "passive"))
      (node (ref "C7") (pin "2") (pinfunction "2_2") (pintype "passive"))
      (node (ref "D22") (pin "C") (pinfunction "C_C") (pintype "passive"))
      (node (ref "IC2") (pin "2") (pinfunction "VOUT_2") (pintype "output"))
      (node (ref "IC2") (pin "4") (pinfunction "VOUT_4") (pintype "output"))
      (node (ref "L2") (pin "1") (pinfunction "1_1") (pintype "passive"))
      (node (ref "LED_R1C1") (pin "VDD") (pinfunction "VDD_VDD") (pintype "power_in"))
      (node (ref "LED_R1C2") (pin "VDD") (pinfunction "VDD_VDD") (pintype "power_in"))
      (node (ref "LED_R1C3") (pin "VDD") (pinfunction "VDD_VDD") (pintype "power_in"))
      (node (ref "LED_R1C4") (pin "VDD") (pinfunction "VDD_VDD") (pintype "power_in"))
      (node (ref "LED_R2C1") (pin "VDD") (pinfunction "VDD_VDD") (pintype "power_in"))
      (node (ref "LED_R2C2") (pin "VDD") (pinfunction "VDD_VDD") (pintype "power_in"))
      (node (ref "LED_R2C3") (pin "VDD") (pinfunction "VDD_VDD") (pintype "power_in"))
      (node (ref "LED_R2C4") (pin "VDD") (pinfunction "VDD_VDD") (pintype "power_in"))
      (node (ref "LED_R3C1") (pin "VDD") (pinfunction "VDD_VDD") (pintype "power_in"))
      (node (ref "LED_R3C2") (pin "VDD") (pinfunction "VDD_VDD") (pintype "power_in"))
      (node (ref "LED_R3C3") (pin "VDD") (pinfunction "VDD_VDD") (pintype "power_in"))
      (node (ref "LED_R3C4") (pin "VDD") (pinfunction "VDD_VDD") (pintype "power_in"))
      (node (ref "LED_R4C1") (pin "VDD") (pinfunction "VDD_VDD") (pintype "power_in"))
      (node (ref "LED_R4C2") (pin "VDD") (pinfunction "VDD_VDD") (pintype "power_in"))
      (node (ref "LED_R4C3") (pin "VDD") (pinfunction "VDD_VDD") (pintype "power_in"))
      (node (ref "LED_R4C4") (pin "VDD") (pinfunction "VDD_VDD") (pintype "power_in"))
      (node (ref "LED_R5C1") (pin "VDD") (pinfunction "VDD_VDD") (pintype "power_in"))
      (node (ref "LED_R5C2") (pin "VDD") (pinfunction "VDD_VDD") (pintype "power_in"))
      (node (ref "LED_R5C3") (pin "VDD") (pinfunction "VDD_VDD") (pintype "power_in"))
      (node (ref "LED_R5C4") (pin "VDD") (pinfunction "VDD_VDD") (pintype "power_in"))
      (node (ref "R11") (pin "1") (pinfunction "1_1") (pintype "passive"))
      (node (ref "R12") (pin "2") (pinfunction "2_2") (pintype "passive"))
      (node (ref "R16") (pin "2") (pinfunction "2_2") (pintype "passive"))
      (node (ref "R2") (pin "1") (pinfunction "1_1") (pintype "passive"))
      (node (ref "SD1") (pin "4") (pinfunction "VDD_4") (pintype "power_in"))
      (node (ref "SH1") (pin "3") (pinfunction "3_3") (pintype "passive"))
      (node (ref "U$2") (pin "4") (pinfunction "VDD_4") (pintype "bidirectional"))
      (node (ref "U19") (pin "4") (pinfunction "EN_4") (pintype "bidirectional"))
      (node (ref "U19") (pin "5") (pinfunction "VIN_5") (pintype "bidirectional"))
      (node (ref "U3") (pin "2") (pinfunction "VDD3P3_2") (pintype "power_in"))
      (node (ref "U3") (pin "20") (pinfunction "VDD3P3_RTC_20") (pintype "power_in"))
      (node (ref "U3") (pin "3") (pinfunction "VDD3P3_3") (pintype "power_in"))
      (node (ref "U3") (pin "46") (pinfunction "VDD3P3_CPU_46") (pintype "power_in"))
      (node (ref "U3") (pin "55") (pinfunction "VDDA1_55") (pintype "power_in"))
      (node (ref "U3") (pin "56") (pinfunction "VDDA2_56") (pintype "power_in"))
    )
    (net (code "2") (name "/CARD_DET") (class "Default")
      (node (ref "SD1") (pin "9") (pinfunction "~{CARD}_9") (pintype "passive"))
      (node (ref "U3") (pin "11") (pinfunction "GPIO6_11") (pintype "bidirectional"))
    )
    (net (code "3") (name "/SD_CLK") (class "Default")
      (node (ref "SD1") (pin "5") (pinfunction "CLK(SCLK)_5") (pintype "input"))
      (node (ref "U3") (pin "13") (pinfunction "GPIO8_13") (pintype "bidirectional"))
    )
    (net (code "4") (name "/SD_CMD") (class "Default")
      (node (ref "SD1") (pin "3") (pinfunction "CMD(DI)_3") (pintype "bidirectional"))
      (node (ref "U3") (pin "14") (pinfunction "GPIO9_14") (pintype "bidirectional"))
    )
    (net (code "5") (name "/SD_D0") (class "Default")
      (node (ref "SD1") (pin "7") (pinfunction "DAT0(DO)_7") (pintype "bidirectional"))
      (node (ref "U3") (pin "12") (pinfunction "GPIO7_12") (pintype "bidirectional"))
    )
    (net (code "6") (name "/USB_DN") (class "Default")
      (node (ref "U2") (pin "A7") (pinfunction "DN1_A7") (pintype "bidirectional"))
      (node (ref "U2") (pin "B7") (pinfunction "DN2_B7") (pintype "bidirectional"))
      (node (ref "U3") (pin "25") (pinfunction "GPIO19_25") (pintype "bidirectional"))
    )
    (net (code "7") (name "/USB_DP") (class "Default")
      (node (ref "U2") (pin "A6") (pinfunction "DP1_A6") (pintype "bidirectional"))
      (node (ref "U2") (pin "B6") (pinfunction "DP2_B6") (pintype "bidirectional"))
      (node (ref "U3") (pin "26") (pinfunction "GPIO20_26") (pintype "bidirectional"))
    )
    (net (code "8") (name "/VDD_SPI") (class "Default")
      (node (ref "U3") (pin "29") (pinfunction "VDD_SPI_29") (pintype "power_in"))
    )
    (net (code "9") (name "12V") (class "Default")
      (node (ref "C31") (pin "2") (pinfunction "2_2") (pintype "passive"))
      (node (ref "C35") (pin "2") (pinfunction "2_2") (pintype "passive"))
      (node (ref "C40") (pin "2") (pinfunction "2_2") (pintype "passive"))
      (node (ref "C46") (pin "2") (pinfunction "2_2") (pintype "passive"))
      (node (ref "D1") (pin "C") (pinfunction "C_C") (pintype "passive"))
      (node (ref "R7") (pin "1") (pinfunction "1_1") (pintype "passive"))
      (node (ref "U$2") (pin "11") (pinfunction "VCC2_11") (pintype "bidirectional"))
      (node (ref "U$2") (pin "2") (pinfunction "VCC_2") (pintype "bidirectional"))
    )
    (net (code "10") (name "AUX_DN") (class "Default")
      (node (ref "U1") (pin "A7") (pinfunction "DN1_A7") (pintype "bidirectional"))
      (node (ref "U1") (pin "B7") (pinfunction "DN2_B7") (pintype "bidirectional"))
      (node (ref "U3") (pin "21") (pinfunction "XTAL_32K_P_21") (pintype "bidirectional"))
    )
    (net (code "11") (name "AUX_DP") (class "Default")
      (node (ref "U1") (pin "A6") (pinfunction "DP1_A6") (pintype "bidirectional"))
      (node (ref "U1") (pin "B6") (pinfunction "DP2_B6") (pintype "bidirectional"))
      (node (ref "U3") (pin "22") (pinfunction "XTAL_32K_N_22") (pintype "bidirectional"))
    )
    (net (code "12") (name "COL0") (class "Default")
      (node (ref "SWR1C1") (pin "1") (pinfunction "2_1") (pintype "passive"))
      (node (ref "SWR2C1") (pin "1") (pinfunction "2_1") (pintype "passive"))
      (node (ref "SWR3C1") (pin "1") (pinfunction "2_1") (pintype "passive"))
      (node (ref "SWR4C1") (pin "1") (pinfunction "2_1") (pintype "passive"))
      (node (ref "SWR5C1") (pin "1") (pinfunction "2_1") (pintype "passive"))
      (node (ref "U3") (pin "48") (pinfunction "MTMS_48") (pintype "bidirectional"))
    )
    (net (code "13") (name "COL1") (class "Default")
      (node (ref "SWR1C2") (pin "1") (pinfunction "2_1") (pintype "passive"))
      (node (ref "SWR2C2") (pin "1") (pinfunction "2_1") (pintype "passive"))
      (node (ref "SWR3C2") (pin "1") (pinfunction "2_1") (pintype "passive"))
      (node (ref "SWR4C2") (pin "1") (pinfunction "2_1") (pintype "passive"))
      (node (ref "SWR5C2") (pin "1") (pinfunction "2_1") (pintype "passive"))
      (node (ref "U3") (pin "47") (pinfunction "MTDI_47") (pintype "bidirectional"))
    )
    (net (code "14") (name "COL2") (class "Default")
      (node (ref "SWR1C3") (pin "1") (pinfunction "2_1") (pintype "passive"))
      (node (ref "SWR2C3") (pin "1") (pinfunction "2_1") (pintype "passive"))
      (node (ref "SWR3C3") (pin "1") (pinfunction "2_1") (pintype "passive"))
      (node (ref "SWR4C3") (pin "1") (pinfunction "2_1") (pintype "passive"))
      (node (ref "SWR5C3") (pin "1") (pinfunction "2_1") (pintype "passive"))
      (node (ref "U3") (pin "44") (pinfunction "MTCK_44") (pintype "bidirectional"))
    )
    (net (code "15") (name "COL3") (class "Default")
      (node (ref "SWR1C4") (pin "1") (pinfunction "2_1") (pintype "passive"))
      (node (ref "SWR2C4") (pin "1") (pinfunction "2_1") (pintype "passive"))
      (node (ref "SWR3C4") (pin "1") (pinfunction "2_1") (pintype "passive"))
      (node (ref "SWR4C4") (pin "1") (pinfunction "2_1") (pintype "passive"))
      (node (ref "SWR5C4") (pin "1") (pinfunction "2_1") (pintype "passive"))
      (node (ref "U3") (pin "43") (pinfunction "GPIO38_43") (pintype "bidirectional"))
    )
    (net (code "16") (name "DC") (class "Default")
      (node (ref "U$2") (pin "8") (pinfunction "DC_8") (pintype "bidirectional"))
      (node (ref "U3") (pin "17") (pinfunction "GPIO12_17") (pintype "bidirectional"))
    )
    (net (code "17") (name "GND") (class "Default")
      (node (ref "C1") (pin "1") (pinfunction "1_1") (pintype "passive"))
      (node (ref "C10") (pin "1") (pinfunction "1_1") (pintype "passive"))
      (node (ref "C11") (pin "1") (pinfunction "1_1") (pintype "passive"))
      (node (ref "C12") (pin "1") (pinfunction "1_1") (pintype "passive"))
      (node (ref "C13") (pin "1") (pinfunction "1_1") (pintype "passive"))
      (node (ref "C14") (pin "1") (pinfunction "1_1") (pintype "passive"))
      (node (ref "C15") (pin "1") (pinfunction "1_1") (pintype "passive"))
      (node (ref "C16") (pin "1") (pinfunction "1_1") (pintype "passive"))
      (node (ref "C17") (pin "1") (pinfunction "1_1") (pintype "passive"))
      (node (ref "C18") (pin "1") (pinfunction "1_1") (pintype "passive"))
      (node (ref "C19") (pin "1") (pinfunction "1_1") (pintype "passive"))
      (node (ref "C2") (pin "1") (pinfunction "1_1") (pintype "passive"))
      (node (ref "C20") (pin "1") (pinfunction "1_1") (pintype "passive"))
      (node (ref "C21") (pin "1") (pinfunction "1_1") (pintype "passive"))
      (node (ref "C22") (pin "1") (pinfunction "1_1") (pintype "passive"))
      (node (ref "C23") (pin "1") (pinfunction "1_1") (pintype "passive"))
      (node (ref "C24") (pin "1") (pinfunction "1_1") (pintype "passive"))
      (node (ref "C25") (pin "1") (pinfunction "1_1") (pintype "passive"))
      (node (ref "C26") (pin "1") (pinfunction "1_1") (pintype "passive"))
      (node (ref "C27") (pin "2") (pinfunction "2_2") (pintype "passive"))
      (node (ref "C28") (pin "1") (pinfunction "1_1") (pintype "passive"))
      (node (ref "C29") (pin "1") (pinfunction "1_1") (pintype "passive"))
      (node (ref "C3") (pin "2") (pinfunction "2_2") (pintype "passive"))
      (node (ref "C31") (pin "1") (pinfunction "1_1") (pintype "passive"))
      (node (ref "C33") (pin "1") (pinfunction "1_1") (pintype "passive"))
      (node (ref "C34") (pin "1") (pinfunction "1_1") (pintype "passive"))
      (node (ref "C36") (pin "1") (pinfunction "1_1") (pintype "passive"))
      (node (ref "C37") (pin "1") (pinfunction "1_1") (pintype "passive"))
      (node (ref "C38") (pin "1") (pinfunction "1_1") (pintype "passive"))
      (node (ref "C39") (pin "1") (pinfunction "1_1") (pintype "passive"))
      (node (ref "C4") (pin "2") (pinfunction "2_2") (pintype "passive"))
      (node (ref "C40") (pin "1") (pinfunction "1_1") (pintype "passive"))
      (node (ref "C41") (pin "1") (pinfunction "1_1") (pintype "passive"))
      (node (ref "C42") (pin "1") (pinfunction "1_1") (pintype "passive"))
      (node (ref "C43") (pin "1") (pinfunction "1_1") (pintype "passive"))
      (node (ref "C44") (pin "1") (pinfunction "1_1") (pintype "passive"))
      (node (ref "C45") (pin "1") (pinfunction "1_1") (pintype "passive"))
      (node (ref "C46") (pin "1") (pinfunction "1_1") (pintype "passive"))
      (node (ref "C5") (pin "1") (pinfunction "1_1") (pintype "passive"))
      (node (ref "C6") (pin "1") (pinfunction "1_1") (pintype "passive"))
      (node (ref "C7") (pin "1") (pinfunction "1_1") (pintype "passive"))
      (node (ref "C8") (pin "2") (pinfunction "2_2") (pintype "passive"))
      (node (ref "C9") (pin "1") (pinfunction "1_1") (pintype "passive"))
      (node (ref "IC2") (pin "1") (pinfunction "GND_1") (pintype "power_in"))
      (node (ref "LED_R1C1") (pin "GND") (pinfunction "GND_GND") (pintype "power_in"))
      (node (ref "LED_R1C2") (pin "GND") (pinfunction "GND_GND") (pintype "power_in"))
      (node (ref "LED_R1C3") (pin "GND") (pinfunction "GND_GND") (pintype "power_in"))
      (node (ref "LED_R1C4") (pin "GND") (pinfunction "GND_GND") (pintype "power_in"))
      (node (ref "LED_R2C1") (pin "GND") (pinfunction "GND_GND") (pintype "power_in"))
      (node (ref "LED_R2C2") (pin "GND") (pinfunction "GND_GND") (pintype "power_in"))
      (node (ref "LED_R2C3") (pin "GND") (pinfunction "GND_GND") (pintype "power_in"))
      (node (ref "LED_R2C4") (pin "GND") (pinfunction "GND_GND") (pintype "power_in"))
      (node (ref "LED_R3C1") (pin "GND") (pinfunction "GND_GND") (pintype "power_in"))
      (node (ref "LED_R3C2") (pin "GND") (pinfunction "GND_GND") (pintype "power_in"))
      (node (ref "LED_R3C3") (pin "GND") (pinfunction "GND_GND") (pintype "power_in"))
      (node (ref "LED_R3C4") (pin "GND") (pinfunction "GND_GND") (pintype "power_in"))
      (node (ref "LED_R4C1") (pin "GND") (pinfunction "GND_GND") (pintype "power_in"))
      (node (ref "LED_R4C2") (pin "GND") (pinfunction "GND_GND") (pintype "power_in"))
      (node (ref "LED_R4C3") (pin "GND") (pinfunction "GND_GND") (pintype "power_in"))
      (node (ref "LED_R4C4") (pin "GND") (pinfunction "GND_GND") (pintype "power_in"))
      (node (ref "LED_R5C1") (pin "GND") (pinfunction "GND_GND") (pintype "power_in"))
      (node (ref "LED_R5C2") (pin "GND") (pinfunction "GND_GND") (pintype "power_in"))
      (node (ref "LED_R5C3") (pin "GND") (pinfunction "GND_GND") (pintype "power_in"))
      (node (ref "LED_R5C4") (pin "GND") (pinfunction "GND_GND") (pintype "power_in"))
      (node (ref "Q1") (pin "2") (pinfunction "S_2") (pintype "passive"))
      (node (ref "R1") (pin "2") (pinfunction "2_2") (pintype "passive"))
      (node (ref "R10") (pin "2") (pinfunction "2_2") (pintype "passive"))
      (node (ref "R17") (pin "1") (pinfunction "1_1") (pintype "passive"))
      (node (ref "R18") (pin "1") (pinfunction "1_1") (pintype "passive"))
      (node (ref "R19") (pin "1") (pinfunction "1_1") (pintype "passive"))
      (node (ref "R4") (pin "1") (pinfunction "1_1") (pintype "passive"))
      (node (ref "R5") (pin "1") (pinfunction "1_1") (pintype "passive"))
      (node (ref "R6") (pin "1") (pinfunction "1_1") (pintype "passive"))
      (node (ref "R9") (pin "2") (pinfunction "2_2") (pintype "passive"))
      (node (ref "SD1") (pin "6") (pinfunction "VSS_6") (pintype "power_in"))
      (node (ref "SD1") (pin "S1") (pinfunction "S1_S1") (pintype "passive"))
      (node (ref "SD1") (pin "S2") (pinfunction "S2_S2") (pintype "passive"))
      (node (ref "SD1") (pin "S3") (pinfunction "S3_S3") (pintype "passive"))
      (node (ref "SD1") (pin "S4") (pinfunction "S4_S4") (pintype "passive"))
      (node (ref "SH1") (pin "2") (pinfunction "2_2") (pintype "passive"))
      (node (ref "SH1") (pin "FIT@1") (pinfunction "11_FIT@1") (pintype "passive"))
      (node (ref "SH1") (pin "FIT@2") (pinfunction "12_FIT@2") (pintype "passive"))
      (node (ref "SW1") (pin "A") (pinfunction "P_A") (pintype "passive"))
      (node (ref "SW1") (pin "A'") (pinfunction "P1_A'") (pintype "passive"))
      (node (ref "SW2") (pin "A") (pinfunction "P_A") (pintype "passive"))
      (node (ref "SW2") (pin "A'") (pinfunction "P1_A'") (pintype "passive"))
      (node (ref "SW21") (pin "C") (pinfunction "C_C") (pintype "passive"))
      (node (ref "SW21") (pin "E") (pinfunction "2_E") (pintype "passive"))
      (node (ref "SW22") (pin "C") (pinfunction "C_C") (pintype "passive"))
      (node (ref "SW22") (pin "E") (pinfunction "2_E") (pintype "passive"))
      (node (ref "SW3") (pin "GND1") (pinfunction "1_GND1") (pintype "bidirectional"))
      (node (ref "SW3") (pin "GND2") (pinfunction "4_GND2") (pintype "bidirectional"))
      (node (ref "SW3") (pin "P$1") (pinfunction "3_P$1") (pintype "bidirectional"))
      (node (ref "U$2") (pin "1") (pinfunction "GND_1") (pintype "bidirectional"))
      (node (ref "U$2") (pin "12") (pinfunction "GND2_12") (pintype "bidirectional"))
      (node (ref "U$2") (pin "31") (pinfunction "SHIELD_31") (pintype "bidirectional"))
      (node (ref "U$2") (pin "32") (pinfunction "SHIELD_32") (pintype "bidirectional"))
      (node (ref "U1") (pin "A1B12") (pinfunction "GND_A1B12") (pintype "bidirectional"))
      (node (ref "U1") (pin "B11A12") (pinfunction "GND_B11A12") (pintype "bidirectional"))
      (node (ref "U1") (pin "P$13") (pinfunction "GND_P$13") (pintype "bidirectional"))
      (node (ref "U1") (pin "P$14") (pinfunction "GND_P$14") (pintype "bidirectional"))
      (node (ref "U1") (pin "P$15") (pinfunction "GND_P$15") (pintype "bidirectional"))
      (node (ref "U1") (pin "P$16") (pinfunction "GND_P$16") (pintype "bidirectional"))
      (node (ref "U19") (pin "2") (pinfunction "GND_2") (pintype "bidirectional"))
      (node (ref "U2") (pin "A1B12") (pinfunction "GND_A1B12") (pintype "bidirectional"))
      (node (ref "U2") (pin "B11A12") (pinfunction "GND_B11A12") (pintype "bidirectional"))
      (node (ref "U2") (pin "P$13") (pinfunction "GND_P$13") (pintype "bidirectional"))
      (node (ref "U2") (pin "P$14") (pinfunction "GND_P$14") (pintype "bidirectional"))
      (node (ref "U2") (pin "P$15") (pinfunction "GND_P$15") (pintype "bidirectional"))
      (node (ref "U2") (pin "P$16") (pinfunction "GND_P$16") (pintype "bidirectional"))
      (node (ref "U3") (pin "57") (pinfunction "GND_57") (pintype "power_in"))
      (node (ref "X1") (pin "1") (pinfunction "GND_1") (pintype "passive"))
      (node (ref "X1") (pin "2") (pinfunction "GND_2") (pintype "passive"))
      (node (ref "X2") (pin "1") (pinfunction "GND_1") (pintype "passive"))
      (node (ref "X2") (pin "2") (pinfunction "GND_2") (pintype "passive"))
      (node (ref "Y1") (pin "2") (pinfunction "3_2") (pintype "passive"))
      (node (ref "Y1") (pin "4") (pinfunction "3_4") (pintype "passive"))
    )
    (net (code "18") (name "HEHE") (class "Default")
      (node (ref "SH1") (pin "4") (pinfunction "4_4") (pintype "passive"))
      (node (ref "U3") (pin "27") (pinfunction "GPIO21_27") (pintype "bidirectional"))
    )
    (net (code "19") (name "MOSI") (class "Default")
      (node (ref "U$2") (pin "10") (pinfunction "D1_10") (pintype "bidirectional"))
      (node (ref "U3") (pin "15") (pinfunction "GPIO10_15") (pintype "bidirectional"))
    )
    (net (code "20") (name "Net-(IC2-VIN)") (class "Default")
      (node (ref "C29") (pin "2") (pinfunction "2_2") (pintype "passive"))
      (node (ref "IC2") (pin "3") (pinfunction "VIN_3") (pintype "input"))
      (node (ref "JP1") (pin "2") (pinfunction "2_2") (pintype "passive"))
      (node (ref "JP2") (pin "2") (pinfunction "2_2") (pintype "passive"))
      (node (ref "SH1") (pin "1") (pinfunction "1_1") (pintype "passive"))
      (node (ref "U1") (pin "A4B9") (pinfunction "VBUS_A4B9") (pintype "bidirectional"))
      (node (ref "U1") (pin "B4A9") (pinfunction "VBUS_B4A9") (pintype "bidirectional"))
    )
    (net (code "21") (name "Net-(JP1-Pad1)") (class "Default")
      (node (ref "JP1") (pin "1") (pinfunction "1_1") (pintype "passive"))
      (node (ref "JP2") (pin "1") (pinfunction "1_1") (pintype "passive"))
      (node (ref "U2") (pin "A4B9") (pinfunction "VBUS_A4B9") (pintype "bidirectional"))
      (node (ref "U2") (pin "B4A9") (pinfunction "VBUS_B4A9") (pintype "bidirectional"))
    )
    (net (code "22") (name "Net-(LED_R1C1-DI)") (class "Default")
      (node (ref "LED_R1C1") (pin "DIN") (pinfunction "DI_DIN") (pintype "input"))
      (node (ref "LED_R1C2") (pin "DOUT") (pinfunction "DO_DOUT") (pintype "output"))
    )
    (net (code "23") (name "Net-(LED_R1C1-DO)") (class "Default")
      (node (ref "LED_R1C1") (pin "DOUT") (pinfunction "DO_DOUT") (pintype "output"))
      (node (ref "LED_R2C1") (pin "DIN") (pinfunction "DI_DIN") (pintype "input"))
    )
    (net (code "24") (name "Net-(LED_R1C2-DI)") (class "Default")
      (node (ref "LED_R1C2") (pin "DIN") (pinfunction "DI_DIN") (pintype "input"))
      (node (ref "LED_R1C3") (pin "DOUT") (pinfunction "DO_DOUT") (pintype "output"))
    )
    (net (code "25") (name "Net-(LED_R1C3-DI)") (class "Default")
      (node (ref "LED_R1C3") (pin "DIN") (pinfunction "DI_DIN") (pintype "input"))
      (node (ref "LED_R1C4") (pin "DOUT") (pinfunction "DO_DOUT") (pintype "output"))
    )
    (net (code "26") (name "Net-(LED_R1C4-DI)") (class "Default")
      (node (ref "LED_R1C4") (pin "DIN") (pinfunction "DI_DIN") (pintype "input"))
      (node (ref "R5") (pin "2") (pinfunction "2_2") (pintype "passive"))
      (node (ref "U3") (pin "52") (pinfunction "GPIO46_52") (pintype "bidirectional"))
    )
    (net (code "27") (name "Net-(LED_R2C1-DO)") (class "Default")
      (node (ref "LED_R2C1") (pin "DOUT") (pinfunction "DO_DOUT") (pintype "output"))
      (node (ref "LED_R2C2") (pin "DIN") (pinfunction "DI_DIN") (pintype "input"))
    )
    (net (code "28") (name "Net-(LED_R2C2-DO)") (class "Default")
      (node (ref "LED_R2C2") (pin "DOUT") (pinfunction "DO_DOUT") (pintype "output"))
      (node (ref "LED_R2C3") (pin "DIN") (pinfunction "DI_DIN") (pintype "input"))
    )
    (net (code "29") (name "Net-(LED_R2C3-DO)") (class "Default")
      (node (ref "LED_R2C3") (pin "DOUT") (pinfunction "DO_DOUT") (pintype "output"))
      (node (ref "LED_R2C4") (pin "DIN") (pinfunction "DI_DIN") (pintype "input"))
    )
    (net (code "30") (name "Net-(LED_R2C4-DO)") (class "Default")
      (node (ref "LED_R2C4") (pin "DOUT") (pinfunction "DO_DOUT") (pintype "output"))
      (node (ref "LED_R3C4") (pin "DIN") (pinfunction "DI_DIN") (pintype "input"))
    )
    (net (code "31") (name "Net-(LED_R3C1-DI)") (class "Default")
      (node (ref "LED_R3C1") (pin "DIN") (pinfunction "DI_DIN") (pintype "input"))
      (node (ref "LED_R3C2") (pin "DOUT") (pinfunction "DO_DOUT") (pintype "output"))
    )
    (net (code "32") (name "Net-(LED_R3C1-DO)") (class "Default")
      (node (ref "LED_R3C1") (pin "DOUT") (pinfunction "DO_DOUT") (pintype "output"))
      (node (ref "LED_R4C1") (pin "DIN") (pinfunction "DI_DIN") (pintype "input"))
    )
    (net (code "33") (name "Net-(LED_R3C2-DI)") (class "Default")
      (node (ref "LED_R3C2") (pin "DIN") (pinfunction "DI_DIN") (pintype "input"))
      (node (ref "LED_R3C3") (pin "DOUT") (pinfunction "DO_DOUT") (pintype "output"))
    )
    (net (code "34") (name "Net-(LED_R3C3-DI)") (class "Default")
      (node (ref "LED_R3C3") (pin "DIN") (pinfunction "DI_DIN") (pintype "input"))
      (node (ref "LED_R3C4") (pin "DOUT") (pinfunction "DO_DOUT") (pintype "output"))
    )
    (net (code "35") (name "Net-(LED_R4C1-DO)") (class "Default")
      (node (ref "LED_R4C1") (pin "DOUT") (pinfunction "DO_DOUT") (pintype "output"))
      (node (ref "LED_R4C2") (pin "DIN") (pinfunction "DI_DIN") (pintype "input"))
    )
    (net (code "36") (name "Net-(LED_R4C2-DO)") (class "Default")
      (node (ref "LED_R4C2") (pin "DOUT") (pinfunction "DO_DOUT") (pintype "output"))
      (node (ref "LED_R4C3") (pin "DIN") (pinfunction "DI_DIN") (pintype "input"))
    )
    (net (code "37") (name "Net-(LED_R4C3-DO)") (class "Default")
      (node (ref "LED_R4C3") (pin "DOUT") (pinfunction "DO_DOUT") (pintype "output"))
      (node (ref "LED_R4C4") (pin "DIN") (pinfunction "DI_DIN") (pintype "input"))
    )
    (net (code "38") (name "Net-(LED_R4C4-DO)") (class "Default")
      (node (ref "LED_R4C4") (pin "DOUT") (pinfunction "DO_DOUT") (pintype "output"))
      (node (ref "LED_R5C4") (pin "DIN") (pinfunction "DI_DIN") (pintype "input"))
    )
    (net (code "39") (name "Net-(LED_R5C1-DI)") (class "Default")
      (node (ref "LED_R5C1") (pin "DIN") (pinfunction "DI_DIN") (pintype "input"))
      (node (ref "LED_R5C2") (pin "DOUT") (pinfunction "DO_DOUT") (pintype "output"))
    )
    (net (code "40") (name "Net-(LED_R5C2-DI)") (class "Default")
      (node (ref "LED_R5C2") (pin "DIN") (pinfunction "DI_DIN") (pintype "input"))
      (node (ref "LED_R5C3") (pin "DOUT") (pinfunction "DO_DOUT") (pintype "output"))
    )
    (net (code "41") (name "Net-(LED_R5C3-DI)") (class "Default")
      (node (ref "LED_R5C3") (pin "DIN") (pinfunction "DI_DIN") (pintype "input"))
      (node (ref "LED_R5C4") (pin "DOUT") (pinfunction "DO_DOUT") (pintype "output"))
    )
    (net (code "42") (name "Net-(Q1-D)") (class "Default")
      (node (ref "BZ1") (pin "MINUS") (pinfunction "MINUS_MINUS") (pintype "bidirectional"))
      (node (ref "D22") (pin "A") (pinfunction "A_A") (pintype "passive"))
      (node (ref "Q1") (pin "3") (pinfunction "D_3") (pintype "passive"))
    )
    (net (code "43") (name "Net-(Q1-G)") (class "Default")
      (node (ref "Q1") (pin "1") (pinfunction "G_1") (pintype "passive"))
      (node (ref "R19") (pin "2") (pinfunction "2_2") (pintype "passive"))
      (node (ref "SH1") (pin "8") (pinfunction "8_8") (pintype "passive"))
      (node (ref "U3") (pin "39") (pinfunction "GPIO34_39") (pintype "bidirectional"))
    )
    (net (code "44") (name "Net-(R8-Pad2)") (class "Default")
      (node (ref "R8") (pin "2") (pinfunction "2_2") (pintype "passive"))
      (node (ref "SW22") (pin "A") (pinfunction "A_A") (pintype "passive"))
    )
    (net (code "45") (name "Net-(R13-Pad2)") (class "Default")
      (node (ref "R13") (pin "2") (pinfunction "2_2") (pintype "passive"))
      (node (ref "SW22") (pin "B") (pinfunction "B_B") (pintype "passive"))
    )
    (net (code "46") (name "Net-(R14-Pad2)") (class "Default")
      (node (ref "R14") (pin "2") (pinfunction "2_2") (pintype "passive"))
      (node (ref "SW21") (pin "A") (pinfunction "A_A") (pintype "passive"))
    )
    (net (code "47") (name "Net-(R15-Pad2)") (class "Default")
      (node (ref "R15") (pin "2") (pinfunction "2_2") (pintype "passive"))
      (node (ref "SW21") (pin "B") (pinfunction "B_B") (pintype "passive"))
    )
    (net (code "48") (name "Net-(SD1-CD{slash}DAT3(~{CS}))") (class "Default")
      (node (ref "R11") (pin "2") (pinfunction "2_2") (pintype "passive"))
      (node (ref "SD1") (pin "2") (pinfunction "CD/DAT3(~{CS})_2") (pintype "bidirectional"))
    )
    (net (code "49") (name "Net-(SW1-S)") (class "Default")
      (node (ref "SW1") (pin "B") (pinfunction "S_B") (pintype "passive"))
      (node (ref "SW1") (pin "B'") (pinfunction "S1_B'") (pintype "passive"))
      (node (ref "U3") (pin "23") (pinfunction "GPIO17_23") (pintype "bidirectional"))
    )
    (net (code "50") (name "Net-(SW2-S)") (class "Default")
      (node (ref "SW2") (pin "B") (pinfunction "S_B") (pintype "passive"))
      (node (ref "SW2") (pin "B'") (pinfunction "S1_B'") (pintype "passive"))
      (node (ref "U3") (pin "24") (pinfunction "GPIO18_24") (pintype "bidirectional"))
    )
    (net (code "51") (name "Net-(SW3-2)") (class "Default")
      (node (ref "C4") (pin "1") (pinfunction "1_1") (pintype "passive"))
      (node (ref "JP4") (pin "1") (pinfunction "1_1") (pintype "passive"))
      (node (ref "R2") (pin "2") (pinfunction "2_2") (pintype "passive"))
      (node (ref "SW3") (pin "P$2") (pinfunction "2_P$2") (pintype "bidirectional"))
      (node (ref "U3") (pin "4") (pinfunction "CHIP_PU_4") (pintype "input"))
    )
    (net (code "52") (name "Net-(SW21B-1)") (class "Default")
      (node (ref "JP4") (pin "2") (pinfunction "2_2") (pintype "passive"))
      (node (ref "R16") (pin "1") (pinfunction "1_1") (pintype "passive"))
      (node (ref "SW21") (pin "D") (pinfunction "1_D") (pintype "passive"))
      (node (ref "U3") (pin "8") (pinfunction "GPIO3_8") (pintype "bidirectional"))
    )
    (net (code "53") (name "Net-(SW22B-1)") (class "Default")
      (node (ref "SW22") (pin "D") (pinfunction "1_D") (pintype "passive"))
      (node (ref "U3") (pin "5") (pinfunction "GPIO0_5") (pintype "bidirectional"))
    )
    (net (code "54") (name "Net-(SWR1C1-1)") (class "Default")
      (node (ref "D2") (pin "A") (pinfunction "A_A") (pintype "passive"))
      (node (ref "SWR1C1") (pin "2") (pinfunction "1_2") (pintype "passive"))
    )
    (net (code "55") (name "Net-(SWR1C2-1)") (class "Default")
      (node (ref "D3") (pin "A") (pinfunction "A_A") (pintype "passive"))
      (node (ref "SWR1C2") (pin "2") (pinfunction "1_2") (pintype "passive"))
    )
    (net (code "56") (name "Net-(SWR1C3-1)") (class "Default")
      (node (ref "D4") (pin "A") (pinfunction "A_A") (pintype "passive"))
      (node (ref "SWR1C3") (pin "2") (pinfunction "1_2") (pintype "passive"))
    )
    (net (code "57") (name "Net-(SWR1C4-1)") (class "Default")
      (node (ref "D5") (pin "A") (pinfunction "A_A") (pintype "passive"))
      (node (ref "SWR1C4") (pin "2") (pinfunction "1_2") (pintype "passive"))
    )
    (net (code "58") (name "Net-(SWR2C1-1)") (class "Default")
      (node (ref "D6") (pin "A") (pinfunction "A_A") (pintype "passive"))
      (node (ref "SWR2C1") (pin "2") (pinfunction "1_2") (pintype "passive"))
    )
    (net (code "59") (name "Net-(SWR2C2-1)") (class "Default")
      (node (ref "D7") (pin "A") (pinfunction "A_A") (pintype "passive"))
      (node (ref "SWR2C2") (pin "2") (pinfunction "1_2") (pintype "passive"))
    )
    (net (code "60") (name "Net-(SWR2C3-1)") (class "Default")
      (node (ref "D8") (pin "A") (pinfunction "A_A") (pintype "passive"))
      (node (ref "SWR2C3") (pin "2") (pinfunction "1_2") (pintype "passive"))
    )
    (net (code "61") (name "Net-(SWR2C4-1)") (class "Default")
      (node (ref "D9") (pin "A") (pinfunction "A_A") (pintype "passive"))
      (node (ref "SWR2C4") (pin "2") (pinfunction "1_2") (pintype "passive"))
    )
    (net (code "62") (name "Net-(SWR3C1-1)") (class "Default")
      (node (ref "D13") (pin "A") (pinfunction "A_A") (pintype "passive"))
      (node (ref "SWR3C1") (pin "2") (pinfunction "1_2") (pintype "passive"))
    )
    (net (code "63") (name "Net-(SWR3C2-1)") (class "Default")
      (node (ref "D12") (pin "A") (pinfunction "A_A") (pintype "passive"))
      (node (ref "SWR3C2") (pin "2") (pinfunction "1_2") (pintype "passive"))
    )
    (net (code "64") (name "Net-(SWR3C3-1)") (class "Default")
      (node (ref "D11") (pin "A") (pinfunction "A_A") (pintype "passive"))
      (node (ref "SWR3C3") (pin "2") (pinfunction "1_2") (pintype "passive"))
    )
    (net (code "65") (name "Net-(SWR3C4-1)") (class "Default")
      (node (ref "D10") (pin "A") (pinfunction "A_A") (pintype "passive"))
      (node (ref "SWR3C4") (pin "2") (pinfunction "1_2") (pintype "passive"))
    )
    (net (code "66") (name "Net-(SWR4C1-1)") (class "Default")
      (node (ref "D14") (pin "A") (pinfunction "A_A") (pintype "passive"))
      (node (ref "SWR4C1") (pin "2") (pinfunction "1_2") (pintype "passive"))
    )
    (net (code "67") (name "Net-(SWR4C2-1)") (class "Default")
      (node (ref "D15") (pin "A") (pinfunction "A_A") (pintype "passive"))
      (node (ref "SWR4C2") (pin "2") (pinfunction "1_2") (pintype "passive"))
    )
    (net (code "68") (name "Net-(SWR4C3-1)") (class "Default")
      (node (ref "D16") (pin "A") (pinfunction "A_A") (pintype "passive"))
      (node (ref "SWR4C3") (pin "2") (pinfunction "1_2") (pintype "passive"))
    )
    (net (code "69") (name "Net-(SWR4C4-1)") (class "Default")
      (node (ref "D17") (pin "A") (pinfunction "A_A") (pintype "passive"))
      (node (ref "SWR4C4") (pin "2") (pinfunction "1_2") (pintype "passive"))
    )
    (net (code "70") (name "Net-(SWR5C1-1)") (class "Default")
      (node (ref "D21") (pin "A") (pinfunction "A_A") (pintype "passive"))
      (node (ref "SWR5C1") (pin "2") (pinfunction "1_2") (pintype "passive"))
    )
    (net (code "71") (name "Net-(SWR5C2-1)") (class "Default")
      (node (ref "D20") (pin "A") (pinfunction "A_A") (pintype "passive"))
      (node (ref "SWR5C2") (pin "2") (pinfunction "1_2") (pintype "passive"))
    )
    (net (code "72") (name "Net-(SWR5C3-1)") (class "Default")
      (node (ref "D19") (pin "A") (pinfunction "A_A") (pintype "passive"))
      (node (ref "SWR5C3") (pin "2") (pinfunction "1_2") (pintype "passive"))
    )
    (net (code "73") (name "Net-(SWR5C4-1)") (class "Default")
      (node (ref "D18") (pin "A") (pinfunction "A_A") (pintype "passive"))
      (node (ref "SWR5C4") (pin "2") (pinfunction "1_2") (pintype "passive"))
    )
    (net (code "74") (name "Net-(U$2-IREF)") (class "Default")
      (node (ref "R6") (pin "2") (pinfunction "2_2") (pintype "passive"))
      (node (ref "U$2") (pin "5") (pinfunction "IREF_5") (pintype "bidirectional"))
    )
    (net (code "75") (name "Net-(U$2-VCOMH)") (class "Default")
      (node (ref "C34") (pin "2") (pinfunction "2_2") (pintype "passive"))
      (node (ref "U$2") (pin "3") (pinfunction "VCOMH_3") (pintype "bidirectional"))
    )
    (net (code "76") (name "Net-(U1-CC1)") (class "Default")
      (node (ref "R4") (pin "2") (pinfunction "2_2") (pintype "passive"))
      (node (ref "U1") (pin "A5") (pinfunction "CC1_A5") (pintype "bidirectional"))
    )
    (net (code "77") (name "Net-(U1-CC2)") (class "Default")
      (node (ref "R18") (pin "2") (pinfunction "2_2") (pintype "passive"))
      (node (ref "U1") (pin "B5") (pinfunction "CC2_B5") (pintype "bidirectional"))
    )
    (net (code "78") (name "Net-(U2-CC1)") (class "Default")
      (node (ref "R9") (pin "1") (pinfunction "1_1") (pintype "passive"))
      (node (ref "U2") (pin "A5") (pinfunction "CC1_A5") (pintype "bidirectional"))
    )
    (net (code "79") (name "Net-(U2-CC2)") (class "Default")
      (node (ref "R1") (pin "1") (pinfunction "1_1") (pintype "passive"))
      (node (ref "U2") (pin "B5") (pinfunction "CC2_B5") (pintype "bidirectional"))
    )
    (net (code "80") (name "Net-(U3-GPIO1)") (class "Default")
      (node (ref "C1") (pin "2") (pinfunction "2_2") (pintype "passive"))
      (node (ref "R8") (pin "1") (pinfunction "1_1") (pintype "passive"))
      (node (ref "U3") (pin "6") (pinfunction "GPIO1_6") (pintype "bidirectional"))
    )
    (net (code "81") (name "Net-(U3-GPIO2)") (class "Default")
      (node (ref "C2") (pin "2") (pinfunction "2_2") (pintype "passive"))
      (node (ref "R13") (pin "1") (pinfunction "1_1") (pintype "passive"))
      (node (ref "U3") (pin "7") (pinfunction "GPIO2_7") (pintype "bidirectional"))
    )
    (net (code "82") (name "Net-(U3-GPIO4)") (class "Default")
      (node (ref "C9") (pin "2") (pinfunction "2_2") (pintype "passive"))
      (node (ref "R14") (pin "1") (pinfunction "1_1") (pintype "passive"))
      (node (ref "U3") (pin "9") (pinfunction "GPIO4_9") (pintype "bidirectional"))
    )
    (net (code "83") (name "Net-(U3-GPIO5)") (class "Default")
      (node (ref "C10") (pin "2") (pinfunction "2_2") (pintype "passive"))
      (node (ref "R15") (pin "1") (pinfunction "1_1") (pintype "passive"))
      (node (ref "U3") (pin "10") (pinfunction "GPIO5_10") (pintype "bidirectional"))
    )
    (net (code "84") (name "Net-(U3-GPIO33)") (class "Default")
      (node (ref "SH1") (pin "7") (pinfunction "7_7") (pintype "passive"))
      (node (ref "U3") (pin "38") (pinfunction "GPIO33_38") (pintype "bidirectional"))
    )
    (net (code "85") (name "Net-(U3-LNA_IN)") (class "Default")
      (node (ref "U3") (pin "1") (pinfunction "LNA_IN_1") (pintype "bidirectional"))
      (node (ref "X1") (pin "3") (pinfunction "SIGNAL_3") (pintype "passive"))
    )
    (net (code "86") (name "Net-(U3-SPICLK_N)") (class "Default")
      (node (ref "SH1") (pin "5") (pinfunction "5_5") (pintype "passive"))
      (node (ref "U3") (pin "36") (pinfunction "SPICLK_N_36") (pintype "bidirectional"))
    )
    (net (code "87") (name "Net-(U3-SPICLK_P)") (class "Default")
      (node (ref "SH1") (pin "6") (pinfunction "6_6") (pintype "passive"))
      (node (ref "U3") (pin "37") (pinfunction "SPICLK_P_37") (pintype "bidirectional"))
    )
    (net (code "88") (name "Net-(U3-U0RXD)") (class "Default")
      (node (ref "SH1") (pin "9") (pinfunction "9_9") (pintype "passive"))
      (node (ref "U3") (pin "50") (pinfunction "U0RXD_50") (pintype "bidirectional"))
    )
    (net (code "89") (name "Net-(U3-U0TXD)") (class "Default")
      (node (ref "SH1") (pin "10") (pinfunction "10_10") (pintype "passive"))
      (node (ref "U3") (pin "49") (pinfunction "U0TXD_49") (pintype "bidirectional"))
    )
    (net (code "90") (name "Net-(U3-XTAL_N)") (class "Default")
      (node (ref "C3") (pin "1") (pinfunction "1_1") (pintype "passive"))
      (node (ref "U3") (pin "53") (pinfunction "XTAL_N_53") (pintype "output"))
      (node (ref "Y1") (pin "3") (pinfunction "2_3") (pintype "passive"))
    )
    (net (code "91") (name "Net-(U3-XTAL_P)") (class "Default")
      (node (ref "C8") (pin "1") (pinfunction "1_1") (pintype "passive"))
      (node (ref "U3") (pin "54") (pinfunction "XTAL_P_54") (pintype "input"))
      (node (ref "Y1") (pin "1") (pinfunction "1_1") (pintype "passive"))
    )
    (net (code "92") (name "Net-(U19-FB)") (class "Default")
      (node (ref "C35") (pin "1") (pinfunction "1_1") (pintype "passive"))
      (node (ref "R10") (pin "1") (pinfunction "1_1") (pintype "passive"))
      (node (ref "R7") (pin "2") (pinfunction "2_2") (pintype "passive"))
      (node (ref "U19") (pin "3") (pinfunction "FB_3") (pintype "bidirectional"))
    )
    (net (code "93") (name "Net-(U19-SW)") (class "Default")
      (node (ref "D1") (pin "A") (pinfunction "A_A") (pintype "passive"))
      (node (ref "L2") (pin "2") (pinfunction "2_2") (pintype "passive"))
      (node (ref "U19") (pin "1") (pinfunction "SW_1") (pintype "bidirectional"))
    )
    (net (code "94") (name "Net-(X2-SIGNAL)") (class "Default")
      (node (ref "R3") (pin "1") (pinfunction "1_1") (pintype "passive"))
      (node (ref "X2") (pin "3") (pinfunction "SIGNAL_3") (pintype "passive"))
    )
    (net (code "95") (name "OLED_CS") (class "Default")
      (node (ref "R12") (pin "1") (pinfunction "1_1") (pintype "passive"))
      (node (ref "U$2") (pin "6") (pinfunction "CS_6") (pintype "bidirectional"))
      (node (ref "U3") (pin "19") (pinfunction "GPIO14_19") (pintype "bidirectional"))
    )
    (net (code "96") (name "OLED_RESET") (class "Default")
      (node (ref "R17") (pin "2") (pinfunction "2_2") (pintype "passive"))
      (node (ref "U$2") (pin "7") (pinfunction "RES_7") (pintype "bidirectional"))
      (node (ref "U3") (pin "18") (pinfunction "GPIO13_18") (pintype "bidirectional"))
    )
    (net (code "97") (name "ROW0") (class "Default")
      (node (ref "D2") (pin "C") (pinfunction "C_C") (pintype "passive"))
      (node (ref "D3") (pin "C") (pinfunction "C_C") (pintype "passive"))
      (node (ref "D4") (pin "C") (pinfunction "C_C") (pintype "passive"))
      (node (ref "D5") (pin "C") (pinfunction "C_C") (pintype "passive"))
      (node (ref "U3") (pin "51") (pinfunction "GPIO45_51") (pintype "bidirectional"))
    )
    (net (code "98") (name "ROW1") (class "Default")
      (node (ref "D6") (pin "C") (pinfunction "C_C") (pintype "passive"))
      (node (ref "D7") (pin "C") (pinfunction "C_C") (pintype "passive"))
      (node (ref "D8") (pin "C") (pinfunction "C_C") (pintype "passive"))
      (node (ref "D9") (pin "C") (pinfunction "C_C") (pintype "passive"))
      (node (ref "U3") (pin "45") (pinfunction "MTDO_45") (pintype "bidirectional"))
    )
    (net (code "99") (name "ROW2") (class "Default")
      (node (ref "D10") (pin "C") (pinfunction "C_C") (pintype "passive"))
      (node (ref "D11") (pin "C") (pinfunction "C_C") (pintype "passive"))
      (node (ref "D12") (pin "C") (pinfunction "C_C") (pintype "passive"))
      (node (ref "D13") (pin "C") (pinfunction "C_C") (pintype "passive"))
      (node (ref "U3") (pin "42") (pinfunction "GPIO37_42") (pintype "bidirectional"))
    )
    (net (code "100") (name "ROW3") (class "Default")
      (node (ref "D14") (pin "C") (pinfunction "C_C") (pintype "passive"))
      (node (ref "D15") (pin "C") (pinfunction "C_C") (pintype "passive"))
      (node (ref "D16") (pin "C") (pinfunction "C_C") (pintype "passive"))
      (node (ref "D17") (pin "C") (pinfunction "C_C") (pintype "passive"))
      (node (ref "U3") (pin "41") (pinfunction "GPIO36_41") (pintype "bidirectional"))
    )
    (net (code "101") (name "ROW4") (class "Default")
      (node (ref "D18") (pin "C") (pinfunction "C_C") (pintype "passive"))
      (node (ref "D19") (pin "C") (pinfunction "C_C") (pintype "passive"))
      (node (ref "D20") (pin "C") (pinfunction "C_C") (pintype "passive"))
      (node (ref "D21") (pin "C") (pinfunction "C_C") (pintype "passive"))
      (node (ref "U3") (pin "40") (pinfunction "GPIO35_40") (pintype "bidirectional"))
    )
    (net (code "102") (name "SCLK") (class "Default")
      (node (ref "U$2") (pin "9") (pinfunction "D0_9") (pintype "bidirectional"))
      (node (ref "U3") (pin "16") (pinfunction "GPIO11_16") (pintype "bidirectional"))
    )
    (net (code "103") (name "unconnected-(JP2-Pad3)") (class "Default")
      (node (ref "JP2") (pin "3") (pinfunction "3_3") (pintype "passive"))
    )
    (net (code "104") (name "unconnected-(LED_R5C1-DO-PadDOUT)") (class "Default")
      (node (ref "LED_R5C1") (pin "DOUT") (pinfunction "DO_DOUT") (pintype "output"))
    )
    (net (code "105") (name "unconnected-(R3-Pad2)") (class "Default")
      (node (ref "R3") (pin "2") (pinfunction "2_2") (pintype "passive"))
    )
    (net (code "106") (name "unconnected-(SD1-DAT1-Pad8)") (class "Default")
      (node (ref "SD1") (pin "8") (pinfunction "DAT1_8") (pintype "bidirectional"))
    )
    (net (code "107") (name "unconnected-(SD1-DAT2-Pad1)") (class "Default")
      (node (ref "SD1") (pin "1") (pinfunction "DAT2_1") (pintype "bidirectional"))
    )
    (net (code "108") (name "unconnected-(U1-SBU1-PadA8)") (class "Default")
      (node (ref "U1") (pin "A8") (pinfunction "SBU1_A8") (pintype "bidirectional"))
    )
    (net (code "109") (name "unconnected-(U1-SBU2-PadB8)") (class "Default")
      (node (ref "U1") (pin "B8") (pinfunction "SBU2_B8") (pintype "bidirectional"))
    )
    (net (code "110") (name "unconnected-(U2-SBU1-PadA8)") (class "Default")
      (node (ref "U2") (pin "A8") (pinfunction "SBU1_A8") (pintype "bidirectional"))
    )
    (net (code "111") (name "unconnected-(U2-SBU2-PadB8)") (class "Default")
      (node (ref "U2") (pin "B8") (pinfunction "SBU2_B8") (pintype "bidirectional"))
    )
    (net (code "112") (name "unconnected-(U3-SPICLK-Pad33)") (class "Default")
      (node (ref "U3") (pin "33") (pinfunction "SPICLK_33") (pintype "bidirectional"))
    )
    (net (code "113") (name "unconnected-(U3-SPICS0-Pad32)") (class "Default")
      (node (ref "U3") (pin "32") (pinfunction "SPICS0_32") (pintype "bidirectional"))
    )
    (net (code "114") (name "unconnected-(U3-SPICS1-Pad28)") (class "Default")
      (node (ref "U3") (pin "28") (pinfunction "SPICS1_28") (pintype "bidirectional"))
    )
    (net (code "115") (name "unconnected-(U3-SPID-Pad35)") (class "Default")
      (node (ref "U3") (pin "35") (pinfunction "SPID_35") (pintype "bidirectional"))
    )
    (net (code "116") (name "unconnected-(U3-SPIHD-Pad30)") (class "Default")
      (node (ref "U3") (pin "30") (pinfunction "SPIHD_30") (pintype "bidirectional"))
    )
    (net (code "117") (name "unconnected-(U3-SPIQ-Pad34)") (class "Default")
      (node (ref "U3") (pin "34") (pinfunction "SPIQ_34") (pintype "bidirectional"))
    )
    (net (code "118") (name "unconnected-(U3-SPIWP-Pad31)") (class "Default")
      (node (ref "U3") (pin "31") (pinfunction "SPIWP_31") (pintype "bidirectional"))
    )
  )
)
